# G3-Sensor.net
KiCad netlist of a schematic drawn in Altium Designer
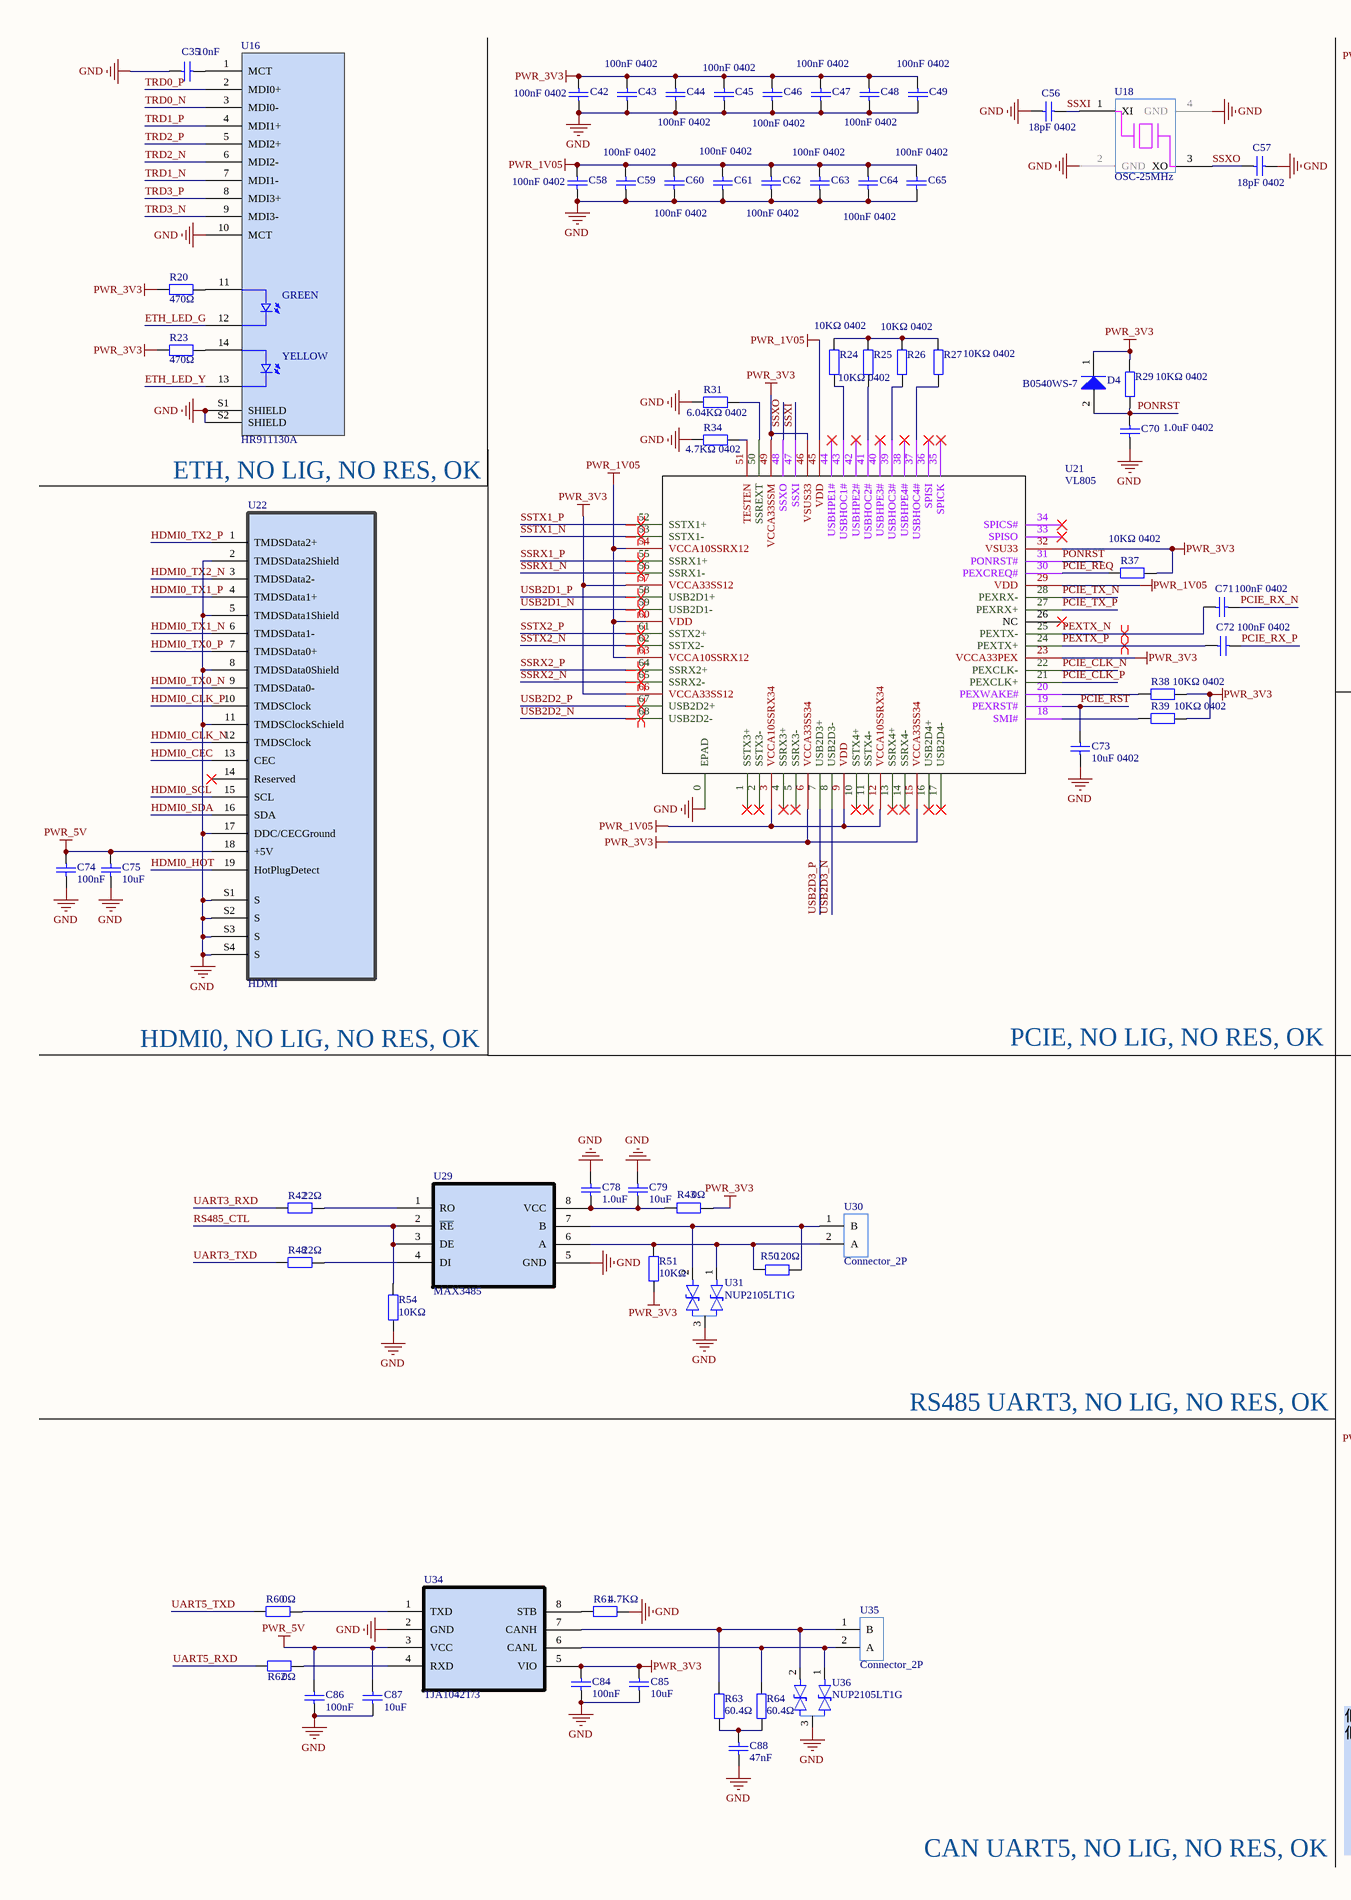
[diagram p0: G3-Sensor.SchDoc, left]
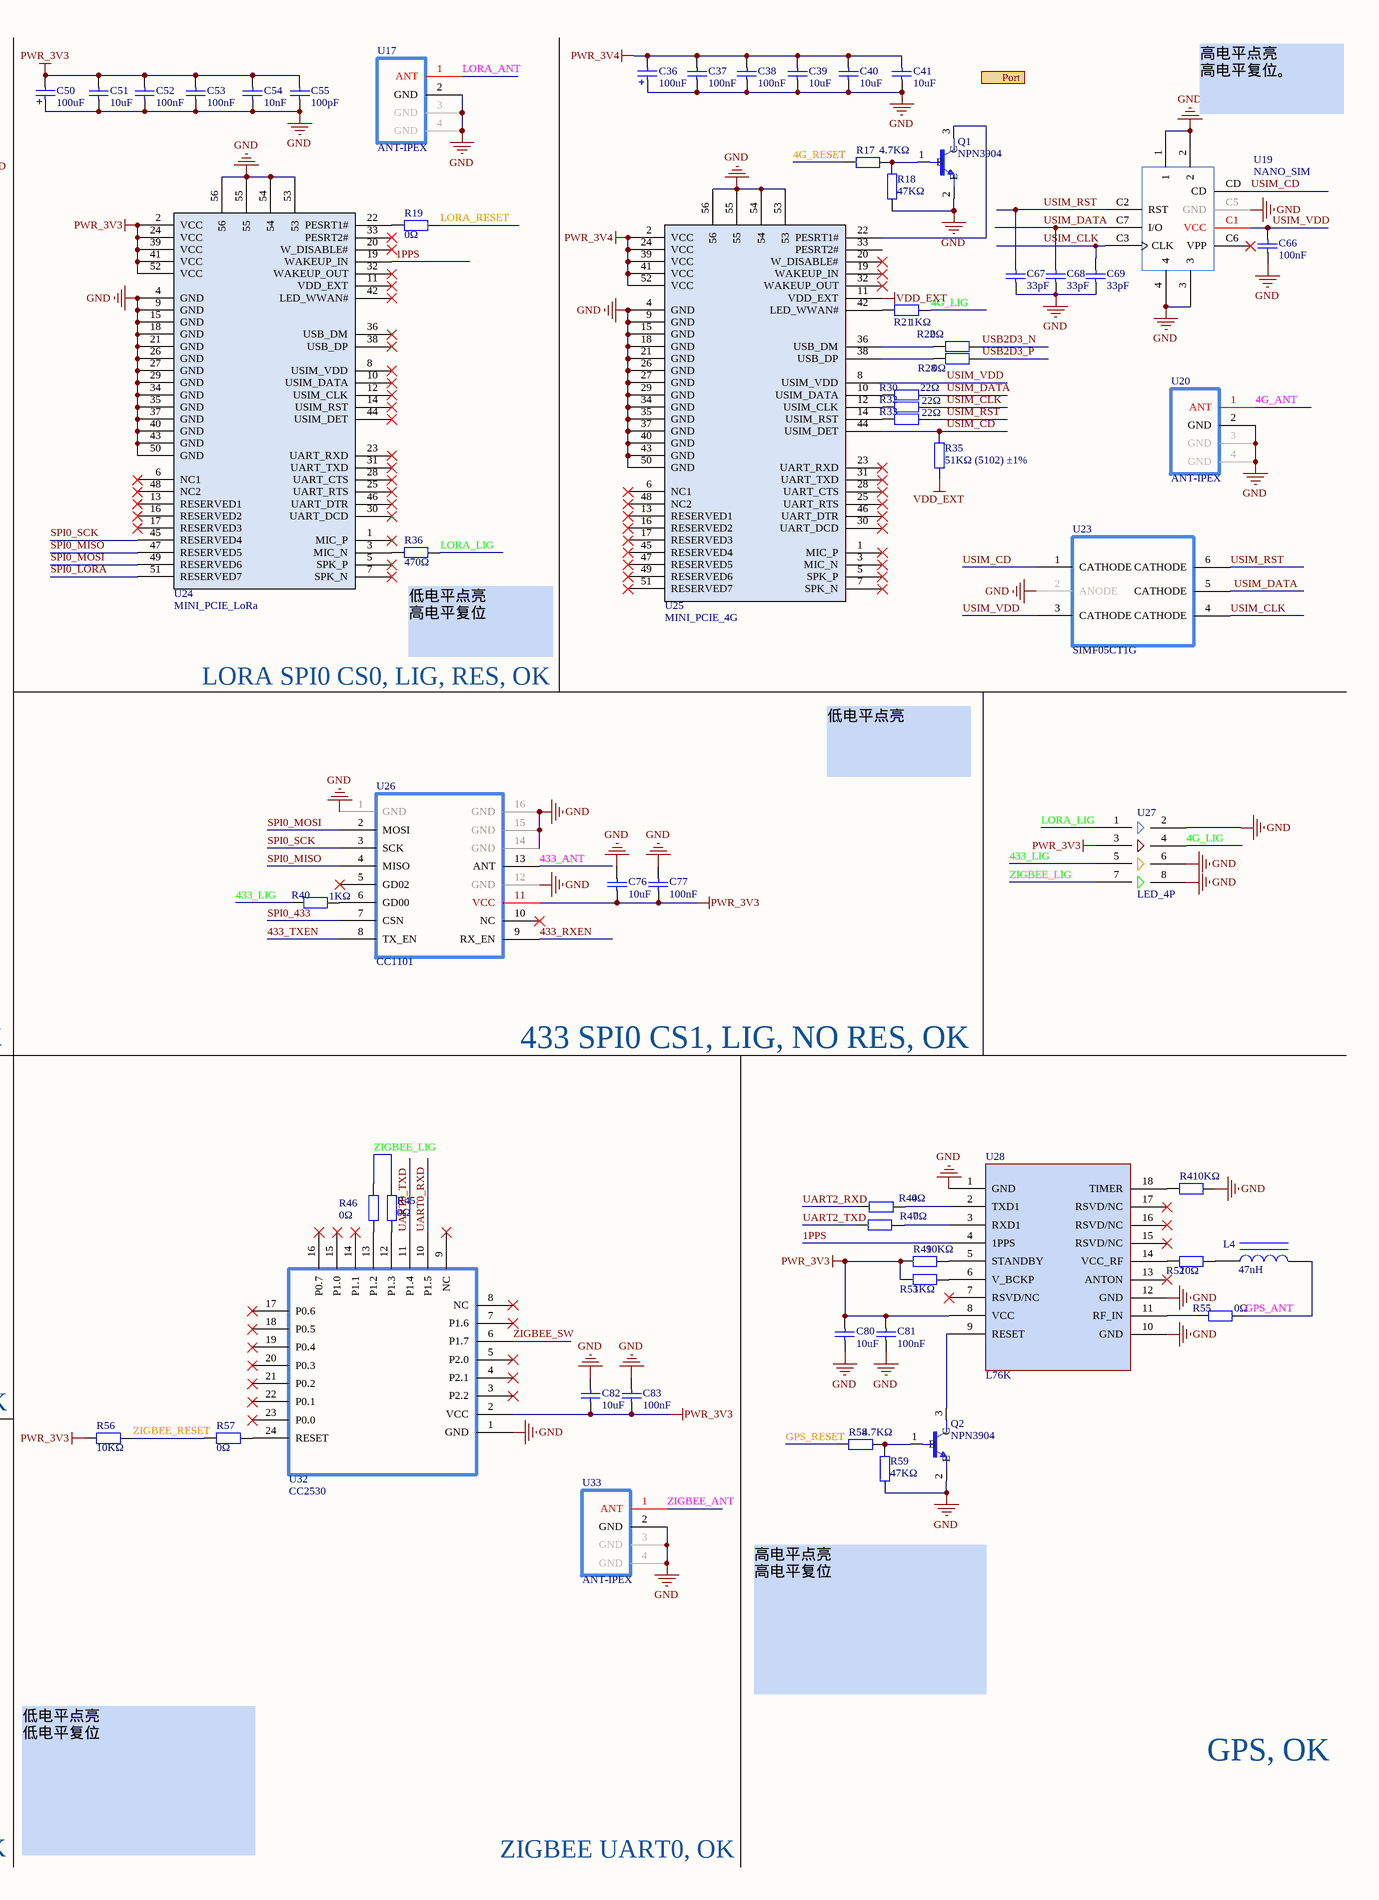
[diagram p1: G3-Sensor.SchDoc, right]

(export (version "E")
  (design (tool "Eeschema 10.0.6"))
  (components
    (comp (ref "C35")
      (value "10nF")
      (footprint "0402_C")
      (description "贴片电容")
      (libsource (lib "Miscellaneous Devices LC") (part "0402 10nF (103) 10% 50V"))
    )
    (comp (ref "C36")
      (value "100uF")
      (footprint "CASE-B_3528")
      (description "钽电容")
      (libsource (lib "Miscellaneous Devices LC") (part "3528 100uF (107) 10% 6.3V"))
    )
    (comp (ref "C37")
      (value "100nF")
      (footprint "1206_C")
      (description "贴片电容")
      (libsource (lib "Miscellaneous Devices LC") (part "1206 100nF (104) 10% 50V"))
    )
    (comp (ref "C38")
      (value "100nF")
      (footprint "1206_C")
      (description "贴片电容")
      (libsource (lib "Miscellaneous Devices LC") (part "1206 100nF (104) 10% 50V"))
    )
    (comp (ref "C39")
      (value "10uF")
      (footprint "1206_C")
      (description "贴片电容")
      (libsource (lib "Miscellaneous Devices LC") (part "1206 10uF (106) 10% 50V"))
    )
    (comp (ref "C40")
      (value "10uF")
      (footprint "1206_C")
      (description "贴片电容")
      (libsource (lib "Miscellaneous Devices LC") (part "1206 10uF (106) 10% 50V"))
    )
    (comp (ref "C41")
      (value "10uF")
      (footprint "1206_C")
      (description "贴片电容")
      (libsource (lib "Miscellaneous Devices LC") (part "1206 10uF (106) 10% 50V"))
    )
    (comp (ref "C42")
      (value "100nF 0402")
      (footprint "0402_C")
      (description "贴片电容")
      (libsource (lib "Miscellaneous Devices LC") (part "0402 100nF (104) 10% 16V"))
    )
    (comp (ref "C43")
      (value "100nF 0402")
      (footprint "0402_C")
      (description "贴片电容")
      (libsource (lib "Miscellaneous Devices LC") (part "0402 100nF (104) 10% 16V"))
    )
    (comp (ref "C44")
      (value "100nF 0402")
      (footprint "0402_C")
      (description "贴片电容")
      (libsource (lib "Miscellaneous Devices LC") (part "0402 100nF (104) 10% 16V"))
    )
    (comp (ref "C45")
      (value "100nF 0402")
      (footprint "0402_C")
      (description "贴片电容")
      (libsource (lib "Miscellaneous Devices LC") (part "0402 100nF (104) 10% 16V"))
    )
    (comp (ref "C46")
      (value "100nF 0402")
      (footprint "0402_C")
      (description "贴片电容")
      (libsource (lib "Miscellaneous Devices LC") (part "0402 100nF (104) 10% 16V"))
    )
    (comp (ref "C47")
      (value "100nF 0402")
      (footprint "0402_C")
      (description "贴片电容")
      (libsource (lib "Miscellaneous Devices LC") (part "0402 100nF (104) 10% 16V"))
    )
    (comp (ref "C48")
      (value "100nF 0402")
      (footprint "0402_C")
      (description "贴片电容")
      (libsource (lib "Miscellaneous Devices LC") (part "0402 100nF (104) 10% 16V"))
    )
    (comp (ref "C49")
      (value "100nF 0402")
      (footprint "0402_C")
      (description "贴片电容")
      (libsource (lib "Miscellaneous Devices LC") (part "0402 100nF (104) 10% 16V"))
    )
    (comp (ref "C50")
      (value "100uF")
      (footprint "CASE-B_3528")
      (description "钽电容")
      (libsource (lib "Miscellaneous Devices LC") (part "3528 100uF (107) 10% 6.3V"))
    )
    (comp (ref "C51")
      (value "10uF")
      (footprint "0402_C")
      (description "贴片电容")
      (libsource (lib "Miscellaneous Devices LC") (part "0402 10uF (106) 20% 6.3V"))
    )
    (comp (ref "C52")
      (value "100nF")
      (footprint "0402_C")
      (description "贴片电容")
      (libsource (lib "Miscellaneous Devices LC") (part "0402 100nF (104) 10% 16V"))
    )
    (comp (ref "C53")
      (value "100nF")
      (footprint "0402_C")
      (description "贴片电容")
      (libsource (lib "Miscellaneous Devices LC") (part "0402 100nF (104) 10% 16V"))
    )
    (comp (ref "C54")
      (value "10nF")
      (footprint "0402_C")
      (description "贴片电容")
      (libsource (lib "Miscellaneous Devices LC") (part "0402 10nF (103) 10% 50V"))
    )
    (comp (ref "C55")
      (value "100pF")
      (footprint "0402_C")
      (description "贴片电容")
      (libsource (lib "Miscellaneous Devices LC") (part "0402 100pF (101) 5% 50V"))
    )
    (comp (ref "C56")
      (value "18pF 0402")
      (footprint "0402_C")
      (description "贴片电容")
      (libsource (lib "Miscellaneous Devices LC") (part "0402 18pF (180) 5% 50V"))
    )
    (comp (ref "C57")
      (value "18pF 0402")
      (footprint "0402_C")
      (description "贴片电容")
      (libsource (lib "Miscellaneous Devices LC") (part "0402 18pF (180) 5% 50V"))
    )
    (comp (ref "C58")
      (value "100nF 0402")
      (footprint "0402_C")
      (description "贴片电容")
      (libsource (lib "Miscellaneous Devices LC") (part "0402 100nF (104) 10% 16V"))
    )
    (comp (ref "C59")
      (value "100nF 0402")
      (footprint "0402_C")
      (description "贴片电容")
      (libsource (lib "Miscellaneous Devices LC") (part "0402 100nF (104) 10% 16V"))
    )
    (comp (ref "C60")
      (value "100nF 0402")
      (footprint "0402_C")
      (description "贴片电容")
      (libsource (lib "Miscellaneous Devices LC") (part "0402 100nF (104) 10% 16V"))
    )
    (comp (ref "C61")
      (value "100nF 0402")
      (footprint "0402_C")
      (description "贴片电容")
      (libsource (lib "Miscellaneous Devices LC") (part "0402 100nF (104) 10% 16V"))
    )
    (comp (ref "C62")
      (value "100nF 0402")
      (footprint "0402_C")
      (description "贴片电容")
      (libsource (lib "Miscellaneous Devices LC") (part "0402 100nF (104) 10% 16V"))
    )
    (comp (ref "C63")
      (value "100nF 0402")
      (footprint "0402_C")
      (description "贴片电容")
      (libsource (lib "Miscellaneous Devices LC") (part "0402 100nF (104) 10% 16V"))
    )
    (comp (ref "C64")
      (value "100nF 0402")
      (footprint "0402_C")
      (description "贴片电容")
      (libsource (lib "Miscellaneous Devices LC") (part "0402 100nF (104) 10% 16V"))
    )
    (comp (ref "C65")
      (value "100nF 0402")
      (footprint "0402_C")
      (description "贴片电容")
      (libsource (lib "Miscellaneous Devices LC") (part "0402 100nF (104) 10% 16V"))
    )
    (comp (ref "C66")
      (value "100nF")
      (footprint "0402_C")
      (description "贴片电容")
      (libsource (lib "Miscellaneous Devices LC") (part "0402 100nF (104) 10% 16V"))
    )
    (comp (ref "C67")
      (value "33pF")
      (footprint "0402_C")
      (description "贴片电容")
      (libsource (lib "Miscellaneous Devices LC") (part "0402 33pF (330) 5% 50V"))
    )
    (comp (ref "C68")
      (value "33pF")
      (footprint "0402_C")
      (description "贴片电容")
      (libsource (lib "Miscellaneous Devices LC") (part "0402 33pF (330) 5% 50V"))
    )
    (comp (ref "C69")
      (value "33pF")
      (footprint "0402_C")
      (description "贴片电容")
      (libsource (lib "Miscellaneous Devices LC") (part "0402 33pF (330) 5% 50V"))
    )
    (comp (ref "C70")
      (value "1.0uF 0402")
      (footprint "0402_C")
      (description "贴片电容")
      (libsource (lib "Miscellaneous Devices LC") (part "0402 1.0uF (105) 10% 25V"))
    )
    (comp (ref "C71")
      (value "100nF 0402")
      (footprint "0402_C")
      (description "贴片电容")
      (libsource (lib "Miscellaneous Devices LC") (part "0402 100nF (104) 10% 16V"))
    )
    (comp (ref "C72")
      (value "100nF 0402")
      (footprint "0402_C")
      (description "贴片电容")
      (libsource (lib "Miscellaneous Devices LC") (part "0402 100nF (104) 10% 16V"))
    )
    (comp (ref "C73")
      (value "10uF 0402")
      (footprint "0402_C")
      (description "贴片电容")
      (libsource (lib "Miscellaneous Devices LC") (part "0402 10uF (106) 20% 6.3V"))
    )
    (comp (ref "C74")
      (value "100nF")
      (footprint "0402_C")
      (description "贴片电容")
      (libsource (lib "Miscellaneous Devices LC") (part "0402 100nF (104) 10% 16V"))
    )
    (comp (ref "C75")
      (value "10uF")
      (footprint "0402_C")
      (description "贴片电容")
      (libsource (lib "Miscellaneous Devices LC") (part "0402 10uF (106) 20% 6.3V"))
    )
    (comp (ref "C76")
      (value "10uF")
      (footprint "0402_C")
      (description "贴片电容")
      (libsource (lib "Miscellaneous Devices LC") (part "0402 10uF (106) 20% 6.3V"))
    )
    (comp (ref "C77")
      (value "100nF")
      (footprint "0402_C")
      (description "贴片电容")
      (libsource (lib "Miscellaneous Devices LC") (part "0402 100nF (104) 10% 16V"))
    )
    (comp (ref "C78")
      (value "1.0uF")
      (footprint "0402_C")
      (description "贴片电容")
      (libsource (lib "Miscellaneous Devices LC") (part "0402 1.0uF (105) 10% 25V"))
    )
    (comp (ref "C79")
      (value "10uF")
      (footprint "0402_C")
      (description "贴片电容")
      (libsource (lib "Miscellaneous Devices LC") (part "0402 10uF (106) 20% 6.3V"))
    )
    (comp (ref "C80")
      (value "10uF")
      (footprint "0402_C")
      (description "贴片电容")
      (libsource (lib "Miscellaneous Devices LC") (part "0402 10uF (106) 20% 6.3V"))
    )
    (comp (ref "C81")
      (value "100nF")
      (footprint "0402_C")
      (description "贴片电容")
      (libsource (lib "Miscellaneous Devices LC") (part "0402 100nF (104) 10% 16V"))
    )
    (comp (ref "C82")
      (value "10uF")
      (footprint "0402_C")
      (description "贴片电容")
      (libsource (lib "Miscellaneous Devices LC") (part "0402 10uF (106) 20% 6.3V"))
    )
    (comp (ref "C83")
      (value "100nF")
      (footprint "0402_C")
      (description "贴片电容")
      (libsource (lib "Miscellaneous Devices LC") (part "0402 100nF (104) 10% 16V"))
    )
    (comp (ref "C84")
      (value "100nF")
      (footprint "0402_C")
      (description "贴片电容")
      (libsource (lib "Miscellaneous Devices LC") (part "0402 100nF (104) 10% 16V"))
    )
    (comp (ref "C85")
      (value "10uF")
      (footprint "0402_C")
      (description "贴片电容")
      (libsource (lib "Miscellaneous Devices LC") (part "0402 10uF (106) 20% 6.3V"))
    )
    (comp (ref "C86")
      (value "100nF")
      (footprint "0402_C")
      (description "贴片电容")
      (libsource (lib "Miscellaneous Devices LC") (part "0402 100nF (104) 10% 16V"))
    )
    (comp (ref "C87")
      (value "10uF")
      (footprint "0402_C")
      (description "贴片电容")
      (libsource (lib "Miscellaneous Devices LC") (part "0402 10uF (106) 20% 6.3V"))
    )
    (comp (ref "C88")
      (value "47nF")
      (footprint "0402_C")
      (description "贴片电容")
      (libsource (lib "Miscellaneous Devices LC") (part "0402 100nF (104) 10% 16V"))
    )
    (comp (ref "D4") (value "B0540WS-7") (footprint "B0540WS-7") (libsource (lib "Mars") (part "B0540WS-7")))
    (comp (ref "L4")
      (value "47nH")
      (footprint "0603_L")
      (description "贴片电感")
      (libsource (lib "Miscellaneous Devices LC") (part "0603 47nH"))
    )
    (comp (ref "Q1")
      (value "NPN3904")
      (footprint "NPN3904")
      (description "Bipolar _BJT_ Transistor NPN 40V 200mA 300MHz 300mW Surface Mount SOT-23-3 _TO-236_")
      (fields (field (name "MF") "ON Semiconductor") (field (name "MP") "MMBT3904LT1G"))
      (libsource (lib "Sensor") (part "NPN3904"))
    )
    (comp (ref "Q2")
      (value "NPN3904")
      (footprint "NPN3904")
      (description "Bipolar _BJT_ Transistor NPN 40V 200mA 300MHz 300mW Surface Mount SOT-23-3 _TO-236_")
      (fields (field (name "MF") "ON Semiconductor") (field (name "MP") "MMBT3904LT1G"))
      (libsource (lib "Sensor") (part "NPN3904"))
    )
    (comp (ref "R17")
      (value "4.7KΩ")
      (footprint "0402_R")
      (description "贴片电阻")
      (libsource (lib "Miscellaneous Devices LC") (part "0402 4.7KΩ (4701) 1%"))
    )
    (comp (ref "R18")
      (value "47KΩ")
      (footprint "0402_R")
      (description "贴片电阻")
      (libsource (lib "Miscellaneous Devices LC") (part "0402 47KΩ (4702) 1%"))
    )
    (comp (ref "R19")
      (value "0Ω")
      (footprint "0402_R")
      (description "贴片电阻")
      (libsource (lib "") (part "0402 0Ω (0R0) 1%_2"))
    )
    (comp (ref "R20")
      (value "470Ω")
      (footprint "0402_R")
      (description "贴片电阻")
      (libsource (lib "Miscellaneous Devices LC") (part "0402 470Ω (4700) 1%"))
    )
    (comp (ref "R21")
      (value "1KΩ")
      (footprint "0402_R")
      (description "贴片电阻")
      (libsource (lib "Miscellaneous Devices LC") (part "0402 1KΩ (1001) 1%"))
    )
    (comp (ref "R22")
      (value "0Ω")
      (footprint "0402_R")
      (description "贴片电阻")
      (libsource (lib "") (part "0402 0Ω (0R0) 1%_2"))
    )
    (comp (ref "R23")
      (value "470Ω")
      (footprint "0402_R")
      (description "贴片电阻")
      (libsource (lib "Miscellaneous Devices LC") (part "0402 470Ω (4700) 1%"))
    )
    (comp (ref "R24")
      (value "10KΩ 0402")
      (footprint "0402_R")
      (description "贴片电阻")
      (libsource (lib "Miscellaneous Devices LC") (part "0402 10KΩ (1002) 1%"))
    )
    (comp (ref "R25")
      (value "10KΩ 0402")
      (footprint "0402_R")
      (description "贴片电阻")
      (libsource (lib "Miscellaneous Devices LC") (part "0402 10KΩ (1002) 1%"))
    )
    (comp (ref "R26")
      (value "10KΩ 0402")
      (footprint "0402_R")
      (description "贴片电阻")
      (libsource (lib "Miscellaneous Devices LC") (part "0402 10KΩ (1002) 1%"))
    )
    (comp (ref "R27")
      (value "10KΩ 0402")
      (footprint "0402_R")
      (description "贴片电阻")
      (libsource (lib "Miscellaneous Devices LC") (part "0402 10KΩ (1002) 1%"))
    )
    (comp (ref "R28")
      (value "0Ω")
      (footprint "0402_R")
      (description "贴片电阻")
      (libsource (lib "Miscellaneous Devices LC") (part "0402 0Ω (0R0) 1%"))
    )
    (comp (ref "R29")
      (value "10KΩ 0402")
      (footprint "0402_R")
      (description "贴片电阻")
      (libsource (lib "Miscellaneous Devices LC") (part "0402 10KΩ (1002) 1%"))
    )
    (comp (ref "R30")
      (value "22Ω")
      (footprint "0402_R")
      (description "贴片电阻")
      (libsource (lib "") (part "0402 22Ω (22R0) 1%_1"))
    )
    (comp (ref "R31")
      (value "6.04KΩ 0402")
      (footprint "0402_R")
      (description "贴片电阻")
      (libsource (lib "Miscellaneous Devices LC") (part "0402 5.6KΩ (5601) 1%"))
    )
    (comp (ref "R32")
      (value "22Ω")
      (footprint "0402_R")
      (description "贴片电阻")
      (libsource (lib "") (part "0402 22Ω (22R0) 1%_1"))
    )
    (comp (ref "R33")
      (value "22Ω")
      (footprint "0402_R")
      (description "贴片电阻")
      (libsource (lib "") (part "0402 22Ω (22R0) 1%_1"))
    )
    (comp (ref "R34")
      (value "4.7KΩ 0402")
      (footprint "0402_R")
      (description "贴片电阻")
      (libsource (lib "") (part "0402 4.7KΩ (4701) 1%_1"))
    )
    (comp (ref "R35")
      (value "51KΩ (5102) ±1%")
      (footprint "0402_R")
      (description "贴片电阻")
      (libsource (lib "Miscellaneous Devices LC") (part "0402 51KΩ (5102) 1%"))
    )
    (comp (ref "R36")
      (value "470Ω")
      (footprint "0402_R")
      (description "贴片电阻")
      (libsource (lib "Miscellaneous Devices LC") (part "0402 470Ω (4700) 1%"))
    )
    (comp (ref "R37")
      (value "10KΩ 0402")
      (footprint "0402_R")
      (description "贴片电阻")
      (libsource (lib "") (part "0402 10KΩ (1002) 1%_1"))
    )
    (comp (ref "R38")
      (value "10KΩ 0402")
      (footprint "0402_R")
      (description "贴片电阻")
      (libsource (lib "") (part "0402 10KΩ (1002) 1%_1"))
    )
    (comp (ref "R39")
      (value "10KΩ 0402")
      (footprint "0402_R")
      (description "贴片电阻")
      (libsource (lib "") (part "0402 10KΩ (1002) 1%_1"))
    )
    (comp (ref "R40")
      (value "1KΩ")
      (footprint "0402_R")
      (description "贴片电阻")
      (libsource (lib "Miscellaneous Devices LC") (part "0402 1KΩ (1001) 1%"))
    )
    (comp (ref "R41")
      (value "10KΩ")
      (footprint "0402_R")
      (description "贴片电阻")
      (libsource (lib "") (part "0402 10KΩ (1002) 1%_1"))
    )
    (comp (ref "R42")
      (value "22Ω")
      (footprint "0402_R")
      (description "贴片电阻")
      (libsource (lib "") (part "0402 22Ω (22R0) 1%_1"))
    )
    (comp (ref "R43")
      (value "0Ω")
      (footprint "0402_R")
      (description "贴片电阻")
      (libsource (lib "Miscellaneous Devices LC") (part "0402 0Ω (0R0) 1%"))
    )
    (comp (ref "R44")
      (value "0Ω")
      (footprint "0402_R")
      (description "贴片电阻")
      (libsource (lib "Miscellaneous Devices LC") (part "0402 0Ω (0R0) 1%"))
    )
    (comp (ref "R45")
      (value "0Ω")
      (footprint "0402_R")
      (description "贴片电阻")
      (libsource (lib "") (part "0402 0Ω (0R0) 1%_1"))
    )
    (comp (ref "R46")
      (value "0Ω")
      (footprint "0402_R")
      (description "贴片电阻")
      (libsource (lib "") (part "0402 0Ω (0R0) 1%_1"))
    )
    (comp (ref "R47")
      (value "0Ω")
      (footprint "0402_R")
      (description "贴片电阻")
      (libsource (lib "Miscellaneous Devices LC") (part "0402 0Ω (0R0) 1%"))
    )
    (comp (ref "R48")
      (value "22Ω")
      (footprint "0402_R")
      (description "贴片电阻")
      (libsource (lib "") (part "0402 22Ω (22R0) 1%_1"))
    )
    (comp (ref "R49")
      (value "10KΩ")
      (footprint "0402_R")
      (description "贴片电阻")
      (libsource (lib "") (part "0402 10KΩ (1002) 1%_1"))
    )
    (comp (ref "R50")
      (value "120Ω")
      (footprint "0402_R")
      (description "贴片电阻")
      (libsource (lib "Miscellaneous Devices LC") (part "0402 120Ω (1200) 1%"))
    )
    (comp (ref "R51")
      (value "10KΩ")
      (footprint "0402_R")
      (description "贴片电阻")
      (libsource (lib "Miscellaneous Devices LC") (part "0402 10KΩ (1002) 1%"))
    )
    (comp (ref "R52")
      (value "10Ω")
      (footprint "0402_R")
      (description "贴片电阻")
      (libsource (lib "Miscellaneous Devices LC") (part "0402 10Ω (10R0) 1%"))
    )
    (comp (ref "R53")
      (value "1KΩ")
      (footprint "0402_R")
      (description "贴片电阻")
      (libsource (lib "Miscellaneous Devices LC") (part "0402 1KΩ (1001) 1%"))
    )
    (comp (ref "R54")
      (value "10KΩ")
      (footprint "0402_R")
      (description "贴片电阻")
      (libsource (lib "Miscellaneous Devices LC") (part "0402 10KΩ (1002) 1%"))
    )
    (comp (ref "R55")
      (value "0Ω")
      (footprint "0402_R")
      (description "贴片电阻")
      (libsource (lib "Miscellaneous Devices LC") (part "0402 0Ω (0R0) 1%"))
    )
    (comp (ref "R56")
      (value "10KΩ")
      (footprint "0402_R")
      (description "贴片电阻")
      (libsource (lib "") (part "0402 10KΩ (1002) 1%_1"))
    )
    (comp (ref "R57")
      (value "0Ω")
      (footprint "0402_R")
      (description "贴片电阻")
      (libsource (lib "") (part "0402 0Ω (0R0) 1%_2"))
    )
    (comp (ref "R58")
      (value "4.7KΩ")
      (footprint "0402_R")
      (description "贴片电阻")
      (libsource (lib "Miscellaneous Devices LC") (part "0402 4.7KΩ (4701) 1%"))
    )
    (comp (ref "R59")
      (value "47KΩ")
      (footprint "0402_R")
      (description "贴片电阻")
      (libsource (lib "Miscellaneous Devices LC") (part "0402 47KΩ (4702) 1%"))
    )
    (comp (ref "R60")
      (value "0Ω")
      (footprint "0402_R")
      (description "贴片电阻")
      (libsource (lib "Miscellaneous Devices LC") (part "0402 0Ω (0R0) 1%"))
    )
    (comp (ref "R61")
      (value "4.7KΩ")
      (footprint "0402_R")
      (description "贴片电阻")
      (libsource (lib "Miscellaneous Devices LC") (part "0402 4.7KΩ (4701) 1%"))
    )
    (comp (ref "R62")
      (value "0Ω")
      (footprint "0402_R")
      (description "贴片电阻")
      (libsource (lib "Miscellaneous Devices LC") (part "0402 0Ω (0R0) 1%"))
    )
    (comp (ref "R63")
      (value "60.4Ω")
      (footprint "0402_R")
      (description "贴片电阻")
      (libsource (lib "Miscellaneous Devices LC") (part "0402 22Ω (22R0) 1%"))
    )
    (comp (ref "R64")
      (value "60.4Ω")
      (footprint "0402_R")
      (description "贴片电阻")
      (libsource (lib "Miscellaneous Devices LC") (part "0402 22Ω (22R0) 1%"))
    )
    (comp (ref "U16")
      (value "HR911130A")
      (footprint "HR911130A")
      (description "RJ45")
      (libsource (lib "bohao") (part "HR911130A"))
    )
    (comp (ref "U17")
      (value "ANT-IPEX")
      (footprint "ANT-IPEX")
      (description "ANT")
      (libsource (lib "Sensor") (part "ANT-IPEX"))
    )
    (comp (ref "U18")
      (value "OSC-25MHz")
      (footprint "OSC-25MHz")
      (description "Passive crystal oscillator")
      (libsource (lib "Mars") (part "OSC-25MHz"))
    )
    (comp (ref "U19")
      (value "NANO_SIM")
      (footprint "NANO_SIM")
      (description "4G Card Slot")
      (libsource (lib "bohao") (part "NANO_SIM"))
    )
    (comp (ref "U20")
      (value "ANT-IPEX")
      (footprint "ANT-IPEX")
      (description "ANT")
      (libsource (lib "Sensor") (part "ANT-IPEX"))
    )
    (comp (ref "U21")
      (value "VL805")
      (footprint "VL805")
      (description "PCIe to USB3.0")
      (libsource (lib "Mars") (part "VL805"))
    )
    (comp (ref "U22") (value "HDMI") (footprint "HDMI") (libsource (lib "bohao") (part "HDMI")))
    (comp (ref "U23")
      (value "SIMF05CT1G")
      (footprint "SMF05CT1G")
      (libsource (lib "bohao") (part "SIMF05CT1G"))
    )
    (comp (ref "U24")
      (value "MINI_PCIE_LoRa")
      (footprint "MINI-PCIE")
      (description "LoRa, 4G")
      (libsource (lib "bohao") (part "MINI_PCIE"))
    )
    (comp (ref "U25")
      (value "MINI_PCIE_4G")
      (footprint "MINI-PCIE")
      (description "LoRa, 4G")
      (libsource (lib "bohao") (part "MINI_PCIE"))
    )
    (comp (ref "U26")
      (value "CC1101")
      (footprint "CC1101")
      (description "433Mhz")
      (libsource (lib "bohao") (part "CC1101"))
    )
    (comp (ref "U27")
      (value "LED_4P")
      (footprint "LED_4P")
      (description "LED")
      (libsource (lib "bohao") (part "LED_4P"))
    )
    (comp (ref "U28")
      (value "L76K")
      (footprint "L76K")
      (description "GPS BEIDOU")
      (libsource (lib "bohao") (part "L76K"))
    )
    (comp (ref "U29")
      (value "MAX3485")
      (footprint "MAX3485")
      (description "UART = RS485")
      (libsource (lib "bohao") (part "MAX3485"))
    )
    (comp (ref "U30")
      (value "Connector_2P")
      (footprint "CONNECTOR_2P")
      (description "Connector for RS485, CAN")
      (libsource (lib "bohao") (part "Connector_2P"))
    )
    (comp (ref "U31")
      (value "NUP2105LT1G")
      (footprint "NUP2105LT1G")
      (libsource (lib "bohao") (part "NUP2105LT1G"))
    )
    (comp (ref "U32")
      (value "CC2530")
      (footprint "CC2530")
      (description "ZigBee 2.4GHz")
      (libsource (lib "bohao") (part "CC2530"))
    )
    (comp (ref "U33")
      (value "ANT-IPEX")
      (footprint "ANT-IPEX")
      (description "ANT")
      (libsource (lib "Sensor") (part "ANT-IPEX"))
    )
    (comp (ref "U34")
      (value "TJA1042T/3")
      (footprint "TJA1042T")
      (description "UART = CAN")
      (libsource (lib "bohao") (part "TJA1042T/3"))
    )
    (comp (ref "U35")
      (value "Connector_2P")
      (footprint "CONNECTOR_2P")
      (description "Connector for RS485, CAN")
      (libsource (lib "bohao") (part "Connector_2P"))
    )
    (comp (ref "U36")
      (value "NUP2105LT1G")
      (footprint "NUP2105LT1G")
      (libsource (lib "bohao") (part "NUP2105LT1G"))
    )
  )
  (nets
    (net (code "1") (name "/1PPS") (class "Default")
      (node (ref "U24") (pin "19") (pinfunction "WAKEUP_IN_19") (pintype "passive"))
      (node (ref "U28") (pin "4") (pinfunction "1PPS_4") (pintype "passive"))
    )
    (net (code "2") (name "/4G_ANT") (class "Default")
      (node (ref "U20") (pin "1") (pinfunction "ANT_1") (pintype "passive"))
    )
    (net (code "3") (name "/4G_LIG") (class "Default")
      (node (ref "R21") (pin "2") (pinfunction "2_2") (pintype "passive"))
      (node (ref "U27") (pin "4") (pintype "passive"))
    )
    (net (code "4") (name "/4G_RESET") (class "Default")
      (node (ref "R17") (pin "1") (pinfunction "1_1") (pintype "passive"))
    )
    (net (code "5") (name "/433_ANT") (class "Default")
      (node (ref "U26") (pin "13") (pinfunction "ANT_13") (pintype "passive"))
    )
    (net (code "6") (name "/433_LIG") (class "Default")
      (node (ref "R40") (pin "1") (pinfunction "1_1") (pintype "passive"))
      (node (ref "U27") (pin "5") (pintype "passive"))
    )
    (net (code "7") (name "/433_RXEN") (class "Default")
      (node (ref "U26") (pin "9") (pinfunction "RX_EN_9") (pintype "passive"))
    )
    (net (code "8") (name "/433_TXEN") (class "Default")
      (node (ref "U26") (pin "8") (pinfunction "TX_EN_8") (pintype "passive"))
    )
    (net (code "9") (name "/ETH_LED_G") (class "Default")
      (node (ref "U16") (pin "12") (pinfunction "12_12") (pintype "passive"))
    )
    (net (code "10") (name "/ETH_LED_Y") (class "Default")
      (node (ref "U16") (pin "13") (pinfunction "13_13") (pintype "passive"))
    )
    (net (code "11") (name "/GPS_ANT") (class "Default")
      (node (ref "L4") (pin "2") (pinfunction "2_2") (pintype "passive"))
      (node (ref "R55") (pin "2") (pinfunction "2_2") (pintype "passive"))
    )
    (net (code "12") (name "/GPS_RESET") (class "Default")
      (node (ref "R58") (pin "1") (pinfunction "1_1") (pintype "passive"))
    )
    (net (code "13") (name "/HDMI0_CEC") (class "Default")
      (node (ref "U22") (pin "13") (pinfunction "CEC_13") (pintype "passive"))
    )
    (net (code "14") (name "/HDMI0_CLK_N") (class "Default")
      (node (ref "U22") (pin "12") (pinfunction "TMDSClock_12") (pintype "passive"))
    )
    (net (code "15") (name "/HDMI0_CLK_P") (class "Default")
      (node (ref "U22") (pin "10") (pinfunction "TMDSClock_10") (pintype "passive"))
    )
    (net (code "16") (name "/HDMI0_HOT") (class "Default")
      (node (ref "U22") (pin "19") (pinfunction "HotPlugDetect_19") (pintype "passive"))
    )
    (net (code "17") (name "/HDMI0_SCL") (class "Default")
      (node (ref "U22") (pin "15") (pinfunction "SCL_15") (pintype "passive"))
    )
    (net (code "18") (name "/HDMI0_SDA") (class "Default")
      (node (ref "U22") (pin "16") (pinfunction "SDA_16") (pintype "passive"))
    )
    (net (code "19") (name "/HDMI0_TX0_N") (class "Default")
      (node (ref "U22") (pin "9") (pinfunction "TMDSData0-_9") (pintype "passive"))
    )
    (net (code "20") (name "/HDMI0_TX0_P") (class "Default")
      (node (ref "U22") (pin "7") (pinfunction "TMDSData0+_7") (pintype "passive"))
    )
    (net (code "21") (name "/HDMI0_TX1_N") (class "Default")
      (node (ref "U22") (pin "6") (pinfunction "TMDSData1-_6") (pintype "passive"))
    )
    (net (code "22") (name "/HDMI0_TX1_P") (class "Default")
      (node (ref "U22") (pin "4") (pinfunction "TMDSData1+_4") (pintype "passive"))
    )
    (net (code "23") (name "/HDMI0_TX2_N") (class "Default")
      (node (ref "U22") (pin "3") (pinfunction "TMDSData2-_3") (pintype "passive"))
    )
    (net (code "24") (name "/HDMI0_TX2_P") (class "Default")
      (node (ref "U22") (pin "1") (pinfunction "TMDSData2+_1") (pintype "passive"))
    )
    (net (code "25") (name "/LORA_ANT") (class "Default")
      (node (ref "U17") (pin "1") (pinfunction "ANT_1") (pintype "passive"))
    )
    (net (code "26") (name "/LORA_LIG") (class "Default")
      (node (ref "R36") (pin "2") (pinfunction "2_2") (pintype "passive"))
      (node (ref "U27") (pin "1") (pintype "passive"))
    )
    (net (code "27") (name "/LORA_RESET") (class "Default")
      (node (ref "R19") (pin "1") (pinfunction "1_1") (pintype "passive"))
    )
    (net (code "28") (name "/PCIE_CLK_N") (class "Default")
      (node (ref "U21") (pin "22") (pinfunction "PEXCLK-_22") (pintype "passive"))
    )
    (net (code "29") (name "/PCIE_CLK_P") (class "Default")
      (node (ref "U21") (pin "21") (pinfunction "PEXCLK+_21") (pintype "passive"))
    )
    (net (code "30") (name "/PCIE_REQ") (class "Default")
      (node (ref "R37") (pin "1") (pinfunction "1_1") (pintype "passive"))
      (node (ref "U21") (pin "30") (pinfunction "PEXCREQ#_30") (pintype "passive"))
    )
    (net (code "31") (name "/PCIE_RST") (class "Default")
      (node (ref "C73") (pin "2") (pinfunction "2_2") (pintype "passive"))
      (node (ref "U21") (pin "19") (pinfunction "PEXRST#_19") (pintype "passive"))
    )
    (net (code "32") (name "/PCIE_RX_N") (class "Default")
      (node (ref "C71") (pin "2") (pinfunction "2_2") (pintype "passive"))
    )
    (net (code "33") (name "/PCIE_RX_P") (class "Default")
      (node (ref "C72") (pin "2") (pinfunction "2_2") (pintype "passive"))
    )
    (net (code "34") (name "/PCIE_TX_N") (class "Default")
      (node (ref "U21") (pin "28") (pinfunction "PEXRX-_28") (pintype "passive"))
    )
    (net (code "35") (name "/PCIE_TX_P") (class "Default")
      (node (ref "U21") (pin "27") (pinfunction "PEXRX+_27") (pintype "passive"))
    )
    (net (code "36") (name "/PEXTX_N") (class "Default")
      (node (ref "C71") (pin "1") (pinfunction "1_1") (pintype "passive"))
      (node (ref "U21") (pin "25") (pinfunction "PEXTX-_25") (pintype "passive"))
    )
    (net (code "37") (name "/PEXTX_P") (class "Default")
      (node (ref "C72") (pin "1") (pinfunction "1_1") (pintype "passive"))
      (node (ref "U21") (pin "24") (pinfunction "PEXTX+_24") (pintype "passive"))
    )
    (net (code "38") (name "/PONRST") (class "Default")
      (node (ref "C70") (pin "1") (pinfunction "1_1") (pintype "passive"))
      (node (ref "D4") (pin "2") (pinfunction "A_2") (pintype "passive"))
      (node (ref "R29") (pin "1") (pinfunction "1_1") (pintype "passive"))
      (node (ref "U21") (pin "31") (pinfunction "PONRST#_31") (pintype "passive"))
    )
    (net (code "40") (name "/RS485_CTL") (class "Default")
      (node (ref "R54") (pin "2") (pinfunction "2_2") (pintype "passive"))
      (node (ref "U29") (pin "2") (pinfunction "~{RE}_2") (pintype "passive"))
      (node (ref "U29") (pin "3") (pinfunction "DE_3") (pintype "passive"))
    )
    (net (code "41") (name "/SPI0_433") (class "Default")
      (node (ref "U26") (pin "7") (pinfunction "CSN_7") (pintype "passive"))
    )
    (net (code "42") (name "/SPI0_LORA") (class "Default")
      (node (ref "U24") (pin "51") (pinfunction "RESERVED7_51") (pintype "passive"))
    )
    (net (code "43") (name "/SPI0_MISO") (class "Default")
      (node (ref "U24") (pin "47") (pinfunction "RESERVED5_47") (pintype "passive"))
      (node (ref "U26") (pin "4") (pinfunction "MISO_4") (pintype "passive"))
    )
    (net (code "44") (name "/SPI0_MOSI") (class "Default")
      (node (ref "U24") (pin "49") (pinfunction "RESERVED6_49") (pintype "passive"))
      (node (ref "U26") (pin "2") (pinfunction "MOSI_2") (pintype "passive"))
    )
    (net (code "45") (name "/SPI0_SCK") (class "Default")
      (node (ref "U24") (pin "45") (pinfunction "RESERVED4_45") (pintype "passive"))
      (node (ref "U26") (pin "3") (pinfunction "SCK_3") (pintype "passive"))
    )
    (net (code "46") (name "/SSRX1_N") (class "Default")
      (node (ref "U21") (pin "56") (pinfunction "SSRX1-_56") (pintype "passive"))
    )
    (net (code "47") (name "/SSRX1_P") (class "Default")
      (node (ref "U21") (pin "55") (pinfunction "SSRX1+_55") (pintype "passive"))
    )
    (net (code "48") (name "/SSRX2_N") (class "Default")
      (node (ref "U21") (pin "65") (pinfunction "SSRX2-_65") (pintype "passive"))
    )
    (net (code "49") (name "/SSRX2_P") (class "Default")
      (node (ref "U21") (pin "64") (pinfunction "SSRX2+_64") (pintype "passive"))
    )
    (net (code "50") (name "/SSTX1_N") (class "Default")
      (node (ref "U21") (pin "53") (pinfunction "SSTX1-_53") (pintype "passive"))
    )
    (net (code "51") (name "/SSTX1_P") (class "Default")
      (node (ref "U21") (pin "52") (pinfunction "SSTX1+_52") (pintype "passive"))
    )
    (net (code "52") (name "/SSTX2_N") (class "Default")
      (node (ref "U21") (pin "62") (pinfunction "SSTX2-_62") (pintype "passive"))
    )
    (net (code "53") (name "/SSTX2_P") (class "Default")
      (node (ref "U21") (pin "61") (pinfunction "SSTX2+_61") (pintype "passive"))
    )
    (net (code "54") (name "/SSXI") (class "Default")
      (node (ref "C56") (pin "2") (pinfunction "2_2") (pintype "passive"))
      (node (ref "U18") (pin "1") (pinfunction "XI_1") (pintype "passive"))
      (node (ref "U21") (pin "47") (pinfunction "SSXI_47") (pintype "passive"))
    )
    (net (code "55") (name "/SSXO") (class "Default")
      (node (ref "C57") (pin "1") (pinfunction "1_1") (pintype "passive"))
      (node (ref "U18") (pin "3") (pinfunction "XO_3") (pintype "passive"))
      (node (ref "U21") (pin "48") (pinfunction "SSXO_48") (pintype "passive"))
    )
    (net (code "56") (name "/TRD0_N") (class "Default")
      (node (ref "U16") (pin "3") (pinfunction "MDI0-_3") (pintype "passive"))
    )
    (net (code "57") (name "/TRD0_P") (class "Default")
      (node (ref "U16") (pin "2") (pinfunction "MDI0+_2") (pintype "passive"))
    )
    (net (code "58") (name "/TRD1_N") (class "Default")
      (node (ref "U16") (pin "7") (pinfunction "MDI1-_7") (pintype "passive"))
    )
    (net (code "59") (name "/TRD1_P") (class "Default")
      (node (ref "U16") (pin "4") (pinfunction "MDI1+_4") (pintype "passive"))
    )
    (net (code "60") (name "/TRD2_N") (class "Default")
      (node (ref "U16") (pin "6") (pinfunction "MDI2-_6") (pintype "passive"))
    )
    (net (code "61") (name "/TRD2_P") (class "Default")
      (node (ref "U16") (pin "5") (pinfunction "MDI2+_5") (pintype "passive"))
    )
    (net (code "62") (name "/TRD3_N") (class "Default")
      (node (ref "U16") (pin "9") (pinfunction "MDI3-_9") (pintype "passive"))
    )
    (net (code "63") (name "/TRD3_P") (class "Default")
      (node (ref "U16") (pin "8") (pinfunction "MDI3+_8") (pintype "passive"))
    )
    (net (code "64") (name "/UART0_RXD") (class "Default")
      (node (ref "U32") (pin "10") (pinfunction "P1.5_10") (pintype "passive"))
    )
    (net (code "65") (name "/UART0_TXD") (class "Default")
      (node (ref "U32") (pin "11") (pinfunction "P1.4_11") (pintype "passive"))
    )
    (net (code "66") (name "/UART2_RXD") (class "Default")
      (node (ref "R44") (pin "1") (pinfunction "1_1") (pintype "passive"))
    )
    (net (code "67") (name "/UART2_TXD") (class "Default")
      (node (ref "R47") (pin "1") (pinfunction "1_1") (pintype "passive"))
    )
    (net (code "68") (name "/UART3_RXD") (class "Default")
      (node (ref "R42") (pin "1") (pinfunction "1_1") (pintype "passive"))
    )
    (net (code "69") (name "/UART3_TXD") (class "Default")
      (node (ref "R48") (pin "1") (pinfunction "1_1") (pintype "passive"))
    )
    (net (code "70") (name "/UART5_RXD") (class "Default")
      (node (ref "R62") (pin "1") (pinfunction "1_1") (pintype "passive"))
    )
    (net (code "71") (name "/UART5_TXD") (class "Default")
      (node (ref "R60") (pin "1") (pinfunction "1_1") (pintype "passive"))
    )
    (net (code "72") (name "/USB2D1_N") (class "Default")
      (node (ref "U21") (pin "59") (pinfunction "USB2D1-_59") (pintype "passive"))
    )
    (net (code "73") (name "/USB2D1_P") (class "Default")
      (node (ref "U21") (pin "58") (pinfunction "USB2D1+_58") (pintype "passive"))
    )
    (net (code "74") (name "/USB2D2_N") (class "Default")
      (node (ref "U21") (pin "68") (pinfunction "USB2D2-_68") (pintype "passive"))
    )
    (net (code "75") (name "/USB2D2_P") (class "Default")
      (node (ref "U21") (pin "67") (pinfunction "USB2D2+_67") (pintype "passive"))
    )
    (net (code "76") (name "/USB2D3_N") (class "Default")
      (node (ref "R22") (pin "1") (pinfunction "1_1") (pintype "passive"))
      (node (ref "U21") (pin "8") (pinfunction "USB2D3-_8") (pintype "passive"))
    )
    (net (code "77") (name "/USB2D3_P") (class "Default")
      (node (ref "R28") (pin "2") (pinfunction "2_2") (pintype "passive"))
      (node (ref "U21") (pin "7") (pinfunction "USB2D3+_7") (pintype "passive"))
    )
    (net (code "78") (name "/USIM_CD") (class "Default")
      (node (ref "R35") (pin "2") (pinfunction "2_2") (pintype "passive"))
      (node (ref "U19") (pin "CD") (pinfunction "CD_CD") (pintype "passive"))
      (node (ref "U23") (pin "1") (pinfunction "CATHODE_1") (pintype "passive"))
      (node (ref "U25") (pin "44") (pinfunction "USIM_DET_44") (pintype "passive"))
    )
    (net (code "79") (name "/USIM_CLK") (class "Default")
      (node (ref "C69") (pin "2") (pinfunction "2_2") (pintype "passive"))
      (node (ref "R32") (pin "2") (pinfunction "2_2") (pintype "passive"))
      (node (ref "U19") (pin "C3") (pinfunction "CLK_C3") (pintype "passive"))
      (node (ref "U23") (pin "4") (pinfunction "CATHODE_4") (pintype "passive"))
    )
    (net (code "80") (name "/USIM_DATA") (class "Default")
      (node (ref "C68") (pin "2") (pinfunction "2_2") (pintype "passive"))
      (node (ref "R30") (pin "2") (pinfunction "2_2") (pintype "passive"))
      (node (ref "U19") (pin "C7") (pinfunction "I/O_C7") (pintype "passive"))
      (node (ref "U23") (pin "5") (pinfunction "CATHODE_5") (pintype "passive"))
    )
    (net (code "81") (name "/USIM_RST") (class "Default")
      (node (ref "C67") (pin "2") (pinfunction "2_2") (pintype "passive"))
      (node (ref "R33") (pin "2") (pinfunction "2_2") (pintype "passive"))
      (node (ref "U19") (pin "C2") (pinfunction "RST_C2") (pintype "passive"))
      (node (ref "U23") (pin "6") (pinfunction "CATHODE_6") (pintype "passive"))
    )
    (net (code "82") (name "/USIM_VDD") (class "Default")
      (node (ref "C66") (pin "2") (pinfunction "2_2") (pintype "passive"))
      (node (ref "U19") (pin "C1") (pinfunction "VCC_C1") (pintype "passive"))
      (node (ref "U23") (pin "3") (pinfunction "CATHODE_3") (pintype "passive"))
      (node (ref "U25") (pin "8") (pinfunction "USIM_VDD_8") (pintype "passive"))
    )
    (net (code "83") (name "/ZIGBEE_ANT") (class "Default")
      (node (ref "U33") (pin "1") (pinfunction "ANT_1") (pintype "passive"))
    )
    (net (code "84") (name "/ZIGBEE_LIG") (class "Default")
      (node (ref "R45") (pin "2") (pinfunction "2_2") (pintype "passive"))
      (node (ref "R46") (pin "2") (pinfunction "2_2") (pintype "passive"))
      (node (ref "U27") (pin "7") (pintype "passive"))
    )
    (net (code "85") (name "/ZIGBEE_RESET") (class "Default")
      (node (ref "R56") (pin "2") (pinfunction "2_2") (pintype "passive"))
      (node (ref "R57") (pin "2") (pinfunction "2_2") (pintype "passive"))
    )
    (net (code "86") (name "/ZIGBEE_SW") (class "Default")
      (node (ref "U32") (pin "6") (pinfunction "P1.7_6") (pintype "passive"))
    )
    (net (code "87") (name "GND") (class "Default")
      (node (ref "C35") (pin "1") (pinfunction "1_1") (pintype "passive"))
      (node (ref "C36") (pin "1") (pinfunction "1_1") (pintype "passive"))
      (node (ref "C37") (pin "1") (pinfunction "1_1") (pintype "passive"))
      (node (ref "C38") (pin "1") (pinfunction "1_1") (pintype "passive"))
      (node (ref "C39") (pin "1") (pinfunction "1_1") (pintype "passive"))
      (node (ref "C40") (pin "1") (pinfunction "1_1") (pintype "passive"))
      (node (ref "C41") (pin "1") (pinfunction "1_1") (pintype "passive"))
      (node (ref "C42") (pin "1") (pinfunction "1_1") (pintype "passive"))
      (node (ref "C43") (pin "1") (pinfunction "1_1") (pintype "passive"))
      (node (ref "C44") (pin "1") (pinfunction "1_1") (pintype "passive"))
      (node (ref "C45") (pin "1") (pinfunction "1_1") (pintype "passive"))
      (node (ref "C46") (pin "1") (pinfunction "1_1") (pintype "passive"))
      (node (ref "C47") (pin "1") (pinfunction "1_1") (pintype "passive"))
      (node (ref "C48") (pin "1") (pinfunction "1_1") (pintype "passive"))
      (node (ref "C49") (pin "1") (pinfunction "1_1") (pintype "passive"))
      (node (ref "C50") (pin "1") (pinfunction "1_1") (pintype "passive"))
      (node (ref "C51") (pin "1") (pinfunction "1_1") (pintype "passive"))
      (node (ref "C52") (pin "1") (pinfunction "1_1") (pintype "passive"))
      (node (ref "C53") (pin "1") (pinfunction "1_1") (pintype "passive"))
      (node (ref "C54") (pin "1") (pinfunction "1_1") (pintype "passive"))
      (node (ref "C55") (pin "1") (pinfunction "1_1") (pintype "passive"))
      (node (ref "C56") (pin "1") (pinfunction "1_1") (pintype "passive"))
      (node (ref "C57") (pin "2") (pinfunction "2_2") (pintype "passive"))
      (node (ref "C58") (pin "1") (pinfunction "1_1") (pintype "passive"))
      (node (ref "C59") (pin "1") (pinfunction "1_1") (pintype "passive"))
      (node (ref "C60") (pin "1") (pinfunction "1_1") (pintype "passive"))
      (node (ref "C61") (pin "1") (pinfunction "1_1") (pintype "passive"))
      (node (ref "C62") (pin "1") (pinfunction "1_1") (pintype "passive"))
      (node (ref "C63") (pin "1") (pinfunction "1_1") (pintype "passive"))
      (node (ref "C64") (pin "1") (pinfunction "1_1") (pintype "passive"))
      (node (ref "C65") (pin "1") (pinfunction "1_1") (pintype "passive"))
      (node (ref "C66") (pin "1") (pinfunction "1_1") (pintype "passive"))
      (node (ref "C67") (pin "1") (pinfunction "1_1") (pintype "passive"))
      (node (ref "C68") (pin "1") (pinfunction "1_1") (pintype "passive"))
      (node (ref "C69") (pin "1") (pinfunction "1_1") (pintype "passive"))
      (node (ref "C70") (pin "2") (pinfunction "2_2") (pintype "passive"))
      (node (ref "C73") (pin "1") (pinfunction "1_1") (pintype "passive"))
      (node (ref "C74") (pin "1") (pinfunction "1_1") (pintype "passive"))
      (node (ref "C75") (pin "1") (pinfunction "1_1") (pintype "passive"))
      (node (ref "C76") (pin "2") (pinfunction "2_2") (pintype "passive"))
      (node (ref "C77") (pin "2") (pinfunction "2_2") (pintype "passive"))
      (node (ref "C78") (pin "2") (pinfunction "2_2") (pintype "passive"))
      (node (ref "C79") (pin "2") (pinfunction "2_2") (pintype "passive"))
      (node (ref "C80") (pin "1") (pinfunction "1_1") (pintype "passive"))
      (node (ref "C81") (pin "1") (pinfunction "1_1") (pintype "passive"))
      (node (ref "C82") (pin "2") (pinfunction "2_2") (pintype "passive"))
      (node (ref "C83") (pin "2") (pinfunction "2_2") (pintype "passive"))
      (node (ref "C84") (pin "1") (pinfunction "1_1") (pintype "passive"))
      (node (ref "C85") (pin "1") (pinfunction "1_1") (pintype "passive"))
      (node (ref "C86") (pin "1") (pinfunction "1_1") (pintype "passive"))
      (node (ref "C87") (pin "1") (pinfunction "1_1") (pintype "passive"))
      (node (ref "C88") (pin "1") (pinfunction "1_1") (pintype "passive"))
      (node (ref "Q1") (pin "2") (pinfunction "E_2") (pintype "passive"))
      (node (ref "Q2") (pin "2") (pinfunction "E_2") (pintype "passive"))
      (node (ref "R18") (pin "1") (pinfunction "1_1") (pintype "passive"))
      (node (ref "R31") (pin "2") (pinfunction "2_2") (pintype "passive"))
      (node (ref "R34") (pin "2") (pinfunction "2_2") (pintype "passive"))
      (node (ref "R41") (pin "2") (pinfunction "2_2") (pintype "passive"))
      (node (ref "R54") (pin "1") (pinfunction "1_1") (pintype "passive"))
      (node (ref "R59") (pin "1") (pinfunction "1_1") (pintype "passive"))
      (node (ref "R61") (pin "2") (pinfunction "2_2") (pintype "passive"))
      (node (ref "U16") (pin "10") (pinfunction "MCT_10") (pintype "passive"))
      (node (ref "U16") (pin "S1") (pinfunction "SHIELD_S1") (pintype "passive"))
      (node (ref "U16") (pin "S2") (pinfunction "SHIELD_S2") (pintype "passive"))
      (node (ref "U17") (pin "2") (pinfunction "GND_2") (pintype "passive"))
      (node (ref "U17") (pin "3") (pinfunction "GND_3") (pintype "passive"))
      (node (ref "U17") (pin "4") (pinfunction "GND_4") (pintype "passive"))
      (node (ref "U18") (pin "2") (pinfunction "GND_2") (pintype "passive"))
      (node (ref "U18") (pin "4") (pinfunction "GND_4") (pintype "passive"))
      (node (ref "U19") (pin "1") (pinfunction "1_1") (pintype "passive"))
      (node (ref "U19") (pin "2") (pinfunction "2_2") (pintype "passive"))
      (node (ref "U19") (pin "3") (pinfunction "3_3") (pintype "passive"))
      (node (ref "U19") (pin "4") (pinfunction "4_4") (pintype "passive"))
      (node (ref "U19") (pin "C5") (pinfunction "GND_C5") (pintype "passive"))
      (node (ref "U20") (pin "2") (pinfunction "GND_2") (pintype "passive"))
      (node (ref "U20") (pin "3") (pinfunction "GND_3") (pintype "passive"))
      (node (ref "U20") (pin "4") (pinfunction "GND_4") (pintype "passive"))
      (node (ref "U21") (pin "0") (pinfunction "EPAD_0") (pintype "passive"))
      (node (ref "U22") (pin "11") (pinfunction "TMDSClockSchield_11") (pintype "passive"))
      (node (ref "U22") (pin "17") (pinfunction "DDC/CECGround_17") (pintype "passive"))
      (node (ref "U22") (pin "2") (pinfunction "TMDSData2Shield_2") (pintype "passive"))
      (node (ref "U22") (pin "5") (pinfunction "TMDSData1Shield_5") (pintype "passive"))
      (node (ref "U22") (pin "8") (pinfunction "TMDSData0Shield_8") (pintype "passive"))
      (node (ref "U22") (pin "S1") (pinfunction "S_S1") (pintype "passive"))
      (node (ref "U22") (pin "S2") (pinfunction "S_S2") (pintype "passive"))
      (node (ref "U22") (pin "S3") (pinfunction "S_S3") (pintype "passive"))
      (node (ref "U22") (pin "S4") (pinfunction "S_S4") (pintype "passive"))
      (node (ref "U23") (pin "2") (pinfunction "ANODE_2") (pintype "passive"))
      (node (ref "U24") (pin "15") (pinfunction "GND_15") (pintype "passive"))
      (node (ref "U24") (pin "18") (pinfunction "GND_18") (pintype "passive"))
      (node (ref "U24") (pin "21") (pinfunction "GND_21") (pintype "passive"))
      (node (ref "U24") (pin "26") (pinfunction "GND_26") (pintype "passive"))
      (node (ref "U24") (pin "27") (pinfunction "GND_27") (pintype "passive"))
      (node (ref "U24") (pin "29") (pinfunction "GND_29") (pintype "passive"))
      (node (ref "U24") (pin "34") (pinfunction "GND_34") (pintype "passive"))
      (node (ref "U24") (pin "35") (pinfunction "GND_35") (pintype "passive"))
      (node (ref "U24") (pin "37") (pinfunction "GND_37") (pintype "passive"))
      (node (ref "U24") (pin "4") (pinfunction "GND_4") (pintype "passive"))
      (node (ref "U24") (pin "40") (pinfunction "GND_40") (pintype "passive"))
      (node (ref "U24") (pin "43") (pinfunction "GND_43") (pintype "passive"))
      (node (ref "U24") (pin "50") (pinfunction "GND_50") (pintype "passive"))
      (node (ref "U24") (pin "53") (pinfunction "53_53") (pintype "passive"))
      (node (ref "U24") (pin "54") (pinfunction "54_54") (pintype "passive"))
      (node (ref "U24") (pin "55") (pinfunction "55_55") (pintype "passive"))
      (node (ref "U24") (pin "56") (pinfunction "56_56") (pintype "passive"))
      (node (ref "U24") (pin "9") (pinfunction "GND_9") (pintype "passive"))
      (node (ref "U25") (pin "15") (pinfunction "GND_15") (pintype "passive"))
      (node (ref "U25") (pin "18") (pinfunction "GND_18") (pintype "passive"))
      (node (ref "U25") (pin "21") (pinfunction "GND_21") (pintype "passive"))
      (node (ref "U25") (pin "26") (pinfunction "GND_26") (pintype "passive"))
      (node (ref "U25") (pin "27") (pinfunction "GND_27") (pintype "passive"))
      (node (ref "U25") (pin "29") (pinfunction "GND_29") (pintype "passive"))
      (node (ref "U25") (pin "34") (pinfunction "GND_34") (pintype "passive"))
      (node (ref "U25") (pin "35") (pinfunction "GND_35") (pintype "passive"))
      (node (ref "U25") (pin "37") (pinfunction "GND_37") (pintype "passive"))
      (node (ref "U25") (pin "4") (pinfunction "GND_4") (pintype "passive"))
      (node (ref "U25") (pin "40") (pinfunction "GND_40") (pintype "passive"))
      (node (ref "U25") (pin "43") (pinfunction "GND_43") (pintype "passive"))
      (node (ref "U25") (pin "50") (pinfunction "GND_50") (pintype "passive"))
      (node (ref "U25") (pin "53") (pinfunction "53_53") (pintype "passive"))
      (node (ref "U25") (pin "54") (pinfunction "54_54") (pintype "passive"))
      (node (ref "U25") (pin "55") (pinfunction "55_55") (pintype "passive"))
      (node (ref "U25") (pin "56") (pinfunction "56_56") (pintype "passive"))
      (node (ref "U25") (pin "9") (pinfunction "GND_9") (pintype "passive"))
      (node (ref "U26") (pin "1") (pinfunction "GND_1") (pintype "passive"))
      (node (ref "U26") (pin "12") (pinfunction "GND_12") (pintype "passive"))
      (node (ref "U26") (pin "14") (pinfunction "GND_14") (pintype "passive"))
      (node (ref "U26") (pin "15") (pinfunction "GND_15") (pintype "passive"))
      (node (ref "U26") (pin "16") (pinfunction "GND_16") (pintype "passive"))
      (node (ref "U27") (pin "2") (pintype "passive"))
      (node (ref "U27") (pin "6") (pintype "passive"))
      (node (ref "U27") (pin "8") (pintype "passive"))
      (node (ref "U28") (pin "1") (pinfunction "GND_1") (pintype "passive"))
      (node (ref "U28") (pin "10") (pinfunction "GND_10") (pintype "passive"))
      (node (ref "U28") (pin "12") (pinfunction "GND_12") (pintype "passive"))
      (node (ref "U29") (pin "5") (pinfunction "GND_5") (pintype "passive"))
      (node (ref "U31") (pin "3") (pintype "passive"))
      (node (ref "U32") (pin "1") (pinfunction "GND_1") (pintype "passive"))
      (node (ref "U33") (pin "2") (pinfunction "GND_2") (pintype "passive"))
      (node (ref "U33") (pin "3") (pinfunction "GND_3") (pintype "passive"))
      (node (ref "U33") (pin "4") (pinfunction "GND_4") (pintype "passive"))
      (node (ref "U34") (pin "2") (pinfunction "GND_2") (pintype "passive"))
      (node (ref "U36") (pin "3") (pintype "passive"))
    )
    (net (code "88") (name "Net-(C35-Pad2)") (class "Default")
      (node (ref "C35") (pin "2") (pinfunction "2_2") (pintype "passive"))
      (node (ref "U16") (pin "1") (pinfunction "MCT_1") (pintype "passive"))
    )
    (net (code "89") (name "Net-(C88-Pad2)") (class "Default")
      (node (ref "C88") (pin "2") (pinfunction "2_2") (pintype "passive"))
      (node (ref "R63") (pin "1") (pinfunction "1_1") (pintype "passive"))
      (node (ref "R64") (pin "1") (pinfunction "1_1") (pintype "passive"))
    )
    (net (code "90") (name "Net-(L4-Pad1)") (class "Default")
      (node (ref "L4") (pin "1") (pinfunction "1_1") (pintype "passive"))
      (node (ref "R52") (pin "2") (pinfunction "2_2") (pintype "passive"))
    )
    (net (code "91") (name "Net-(Q1-B)") (class "Default")
      (node (ref "Q1") (pin "1") (pinfunction "B_1") (pintype "passive"))
      (node (ref "R17") (pin "2") (pinfunction "2_2") (pintype "passive"))
      (node (ref "R18") (pin "2") (pinfunction "2_2") (pintype "passive"))
    )
    (net (code "92") (name "Net-(Q1-C)") (class "Default")
      (node (ref "Q1") (pin "3") (pinfunction "C_3") (pintype "passive"))
      (node (ref "U25") (pin "22") (pinfunction "PESRT1#_22") (pintype "passive"))
    )
    (net (code "93") (name "Net-(Q2-B)") (class "Default")
      (node (ref "Q2") (pin "1") (pinfunction "B_1") (pintype "passive"))
      (node (ref "R58") (pin "2") (pinfunction "2_2") (pintype "passive"))
      (node (ref "R59") (pin "2") (pinfunction "2_2") (pintype "passive"))
    )
    (net (code "94") (name "Net-(Q2-C)") (class "Default")
      (node (ref "Q2") (pin "3") (pinfunction "C_3") (pintype "passive"))
      (node (ref "U28") (pin "9") (pinfunction "RESET_9") (pintype "passive"))
    )
    (net (code "95") (name "Net-(R20-Pad2)") (class "Default")
      (node (ref "R20") (pin "2") (pinfunction "2_2") (pintype "passive"))
      (node (ref "U16") (pin "11") (pinfunction "11_11") (pintype "passive"))
    )
    (net (code "96") (name "Net-(R23-Pad2)") (class "Default")
      (node (ref "R23") (pin "2") (pinfunction "2_2") (pintype "passive"))
      (node (ref "U16") (pin "14") (pinfunction "14_14") (pintype "passive"))
    )
    (net (code "97") (name "Net-(R24-Pad2)") (class "Default")
      (node (ref "R24") (pin "2") (pinfunction "2_2") (pintype "passive"))
      (node (ref "R25") (pin "2") (pinfunction "2_2") (pintype "passive"))
      (node (ref "R26") (pin "2") (pinfunction "2_2") (pintype "passive"))
      (node (ref "R27") (pin "2") (pinfunction "2_2") (pintype "passive"))
    )
    (net (code "98") (name "Net-(U21-PEXWAKE#)") (class "Default")
      (node (ref "R38") (pin "1") (pinfunction "1_1") (pintype "passive"))
      (node (ref "U21") (pin "20") (pinfunction "PEXWAKE#_20") (pintype "passive"))
    )
    (net (code "99") (name "Net-(U21-SMI#)") (class "Default")
      (node (ref "R39") (pin "1") (pinfunction "1_1") (pintype "passive"))
      (node (ref "U21") (pin "18") (pinfunction "SMI#_18") (pintype "passive"))
    )
    (net (code "100") (name "Net-(U21-SSREXT)") (class "Default")
      (node (ref "R31") (pin "1") (pinfunction "1_1") (pintype "passive"))
      (node (ref "U21") (pin "50") (pinfunction "SSREXT_50") (pintype "passive"))
    )
    (net (code "101") (name "Net-(U21-TESTEN)") (class "Default")
      (node (ref "R34") (pin "1") (pinfunction "1_1") (pintype "passive"))
      (node (ref "U21") (pin "51") (pinfunction "TESTEN_51") (pintype "passive"))
    )
    (net (code "102") (name "Net-(U21-USBHOC1#)") (class "Default")
      (node (ref "R24") (pin "1") (pinfunction "1_1") (pintype "passive"))
      (node (ref "U21") (pin "43") (pinfunction "USBHOC1#_43") (pintype "passive"))
    )
    (net (code "103") (name "Net-(U21-USBHOC2#)") (class "Default")
      (node (ref "R25") (pin "1") (pinfunction "1_1") (pintype "passive"))
      (node (ref "U21") (pin "41") (pinfunction "USBHOC2#_41") (pintype "passive"))
    )
    (net (code "104") (name "Net-(U21-USBHOC3#)") (class "Default")
      (node (ref "R26") (pin "1") (pinfunction "1_1") (pintype "passive"))
      (node (ref "U21") (pin "39") (pinfunction "USBHOC3#_39") (pintype "passive"))
    )
    (net (code "105") (name "Net-(U21-USBHOC4#)") (class "Default")
      (node (ref "R27") (pin "1") (pinfunction "1_1") (pintype "passive"))
      (node (ref "U21") (pin "37") (pinfunction "USBHOC4#_37") (pintype "passive"))
    )
    (net (code "106") (name "Net-(U24-MIC_N)") (class "Default")
      (node (ref "R36") (pin "1") (pinfunction "1_1") (pintype "passive"))
      (node (ref "U24") (pin "3") (pinfunction "MIC_N_3") (pintype "passive"))
    )
    (net (code "107") (name "Net-(U24-PESRT1#)") (class "Default")
      (node (ref "R19") (pin "2") (pinfunction "2_2") (pintype "passive"))
      (node (ref "U24") (pin "22") (pinfunction "PESRT1#_22") (pintype "passive"))
    )
    (net (code "108") (name "Net-(U25-LED_WWAN#)") (class "Default")
      (node (ref "R21") (pin "1") (pinfunction "1_1") (pintype "passive"))
      (node (ref "U25") (pin "42") (pinfunction "LED_WWAN#_42") (pintype "passive"))
    )
    (net (code "109") (name "Net-(U25-USB_DM)") (class "Default")
      (node (ref "R22") (pin "2") (pinfunction "2_2") (pintype "passive"))
      (node (ref "U25") (pin "36") (pinfunction "USB_DM_36") (pintype "passive"))
    )
    (net (code "110") (name "Net-(U25-USB_DP)") (class "Default")
      (node (ref "R28") (pin "1") (pinfunction "1_1") (pintype "passive"))
      (node (ref "U25") (pin "38") (pinfunction "USB_DP_38") (pintype "passive"))
    )
    (net (code "111") (name "Net-(U25-USIM_CLK)") (class "Default")
      (node (ref "R32") (pin "1") (pinfunction "1_1") (pintype "passive"))
      (node (ref "U25") (pin "12") (pinfunction "USIM_CLK_12") (pintype "passive"))
    )
    (net (code "112") (name "Net-(U25-USIM_DATA)") (class "Default")
      (node (ref "R30") (pin "1") (pinfunction "1_1") (pintype "passive"))
      (node (ref "U25") (pin "10") (pinfunction "USIM_DATA_10") (pintype "passive"))
    )
    (net (code "113") (name "Net-(U25-USIM_RST)") (class "Default")
      (node (ref "R33") (pin "1") (pinfunction "1_1") (pintype "passive"))
      (node (ref "U25") (pin "14") (pinfunction "USIM_RST_14") (pintype "passive"))
    )
    (net (code "114") (name "Net-(U26-GD00)") (class "Default")
      (node (ref "R40") (pin "2") (pinfunction "2_2") (pintype "passive"))
      (node (ref "U26") (pin "6") (pinfunction "GD00_6") (pintype "passive"))
    )
    (net (code "115") (name "Net-(U28-RF_IN)") (class "Default")
      (node (ref "R55") (pin "1") (pinfunction "1_1") (pintype "passive"))
      (node (ref "U28") (pin "11") (pinfunction "RF_IN_11") (pintype "passive"))
    )
    (net (code "116") (name "Net-(U28-RXD1)") (class "Default")
      (node (ref "R47") (pin "2") (pinfunction "2_2") (pintype "passive"))
      (node (ref "U28") (pin "3") (pinfunction "RXD1_3") (pintype "passive"))
    )
    (net (code "117") (name "Net-(U28-STANDBY)") (class "Default")
      (node (ref "R49") (pin "2") (pinfunction "2_2") (pintype "passive"))
      (node (ref "U28") (pin "5") (pinfunction "STANDBY_5") (pintype "passive"))
    )
    (net (code "118") (name "Net-(U28-TIMER)") (class "Default")
      (node (ref "R41") (pin "1") (pinfunction "1_1") (pintype "passive"))
      (node (ref "U28") (pin "18") (pinfunction "TIMER_18") (pintype "passive"))
    )
    (net (code "119") (name "Net-(U28-TXD1)") (class "Default")
      (node (ref "R44") (pin "2") (pinfunction "2_2") (pintype "passive"))
      (node (ref "U28") (pin "2") (pinfunction "TXD1_2") (pintype "passive"))
    )
    (net (code "120") (name "Net-(U28-VCC_RF)") (class "Default")
      (node (ref "R52") (pin "1") (pinfunction "1_1") (pintype "passive"))
      (node (ref "U28") (pin "14") (pinfunction "VCC_RF_14") (pintype "passive"))
    )
    (net (code "121") (name "Net-(U28-V_BCKP)") (class "Default")
      (node (ref "R53") (pin "2") (pinfunction "2_2") (pintype "passive"))
      (node (ref "U28") (pin "6") (pinfunction "V_BCKP_6") (pintype "passive"))
    )
    (net (code "122") (name "Net-(U29-A)") (class "Default")
      (node (ref "R50") (pin "2") (pinfunction "2_2") (pintype "passive"))
      (node (ref "R51") (pin "2") (pinfunction "2_2") (pintype "passive"))
      (node (ref "U29") (pin "6") (pinfunction "A_6") (pintype "passive"))
      (node (ref "U30") (pin "2") (pinfunction "A_2") (pintype "passive"))
      (node (ref "U31") (pin "1") (pintype "passive"))
    )
    (net (code "123") (name "Net-(U29-B)") (class "Default")
      (node (ref "R50") (pin "1") (pinfunction "1_1") (pintype "passive"))
      (node (ref "U29") (pin "7") (pinfunction "B_7") (pintype "passive"))
      (node (ref "U30") (pin "1") (pinfunction "B_1") (pintype "passive"))
      (node (ref "U31") (pin "2") (pintype "passive"))
    )
    (net (code "124") (name "Net-(U29-DI)") (class "Default")
      (node (ref "R48") (pin "2") (pinfunction "2_2") (pintype "passive"))
      (node (ref "U29") (pin "4") (pinfunction "DI_4") (pintype "passive"))
    )
    (net (code "125") (name "Net-(U29-RO)") (class "Default")
      (node (ref "R42") (pin "2") (pinfunction "2_2") (pintype "passive"))
      (node (ref "U29") (pin "1") (pinfunction "RO_1") (pintype "passive"))
    )
    (net (code "126") (name "Net-(U29-VCC)") (class "Default")
      (node (ref "C78") (pin "1") (pinfunction "1_1") (pintype "passive"))
      (node (ref "C79") (pin "1") (pinfunction "1_1") (pintype "passive"))
      (node (ref "R43") (pin "1") (pinfunction "1_1") (pintype "passive"))
      (node (ref "U29") (pin "8") (pinfunction "VCC_8") (pintype "passive"))
    )
    (net (code "127") (name "Net-(U32-P1.2)") (class "Default")
      (node (ref "R46") (pin "1") (pinfunction "1_1") (pintype "passive"))
      (node (ref "U32") (pin "13") (pinfunction "P1.2_13") (pintype "passive"))
    )
    (net (code "128") (name "Net-(U32-P1.3)") (class "Default")
      (node (ref "R45") (pin "1") (pinfunction "1_1") (pintype "passive"))
      (node (ref "U32") (pin "12") (pinfunction "P1.3_12") (pintype "passive"))
    )
    (net (code "129") (name "Net-(U32-RESET)") (class "Default")
      (node (ref "R57") (pin "1") (pinfunction "1_1") (pintype "passive"))
      (node (ref "U32") (pin "24") (pinfunction "RESET_24") (pintype "passive"))
    )
    (net (code "130") (name "Net-(U34-CANH)") (class "Default")
      (node (ref "R63") (pin "2") (pinfunction "2_2") (pintype "passive"))
      (node (ref "U34") (pin "7") (pinfunction "CANH_7") (pintype "passive"))
      (node (ref "U35") (pin "1") (pinfunction "B_1") (pintype "passive"))
      (node (ref "U36") (pin "2") (pintype "passive"))
    )
    (net (code "131") (name "Net-(U34-CANL)") (class "Default")
      (node (ref "R64") (pin "2") (pinfunction "2_2") (pintype "passive"))
      (node (ref "U34") (pin "6") (pinfunction "CANL_6") (pintype "passive"))
      (node (ref "U35") (pin "2") (pinfunction "A_2") (pintype "passive"))
      (node (ref "U36") (pin "1") (pintype "passive"))
    )
    (net (code "132") (name "Net-(U34-RXD)") (class "Default")
      (node (ref "R62") (pin "2") (pinfunction "2_2") (pintype "passive"))
      (node (ref "U34") (pin "4") (pinfunction "RXD_4") (pintype "passive"))
    )
    (net (code "133") (name "Net-(U34-STB)") (class "Default")
      (node (ref "R61") (pin "1") (pinfunction "1_1") (pintype "passive"))
      (node (ref "U34") (pin "8") (pinfunction "STB_8") (pintype "passive"))
    )
    (net (code "134") (name "Net-(U34-TXD)") (class "Default")
      (node (ref "R60") (pin "2") (pinfunction "2_2") (pintype "passive"))
      (node (ref "U34") (pin "1") (pinfunction "TXD_1") (pintype "passive"))
    )
    (net (code "135") (name "PWR_1V05") (class "Default")
      (node (ref "C58") (pin "2") (pinfunction "2_2") (pintype "passive"))
      (node (ref "C59") (pin "2") (pinfunction "2_2") (pintype "passive"))
      (node (ref "C60") (pin "2") (pinfunction "2_2") (pintype "passive"))
      (node (ref "C61") (pin "2") (pinfunction "2_2") (pintype "passive"))
      (node (ref "C62") (pin "2") (pinfunction "2_2") (pintype "passive"))
      (node (ref "C63") (pin "2") (pinfunction "2_2") (pintype "passive"))
      (node (ref "C64") (pin "2") (pinfunction "2_2") (pintype "passive"))
      (node (ref "C65") (pin "2") (pinfunction "2_2") (pintype "passive"))
      (node (ref "U21") (pin "12") (pinfunction "VCCA10SSRX34_12") (pintype "passive"))
      (node (ref "U21") (pin "29") (pinfunction "VDD_29") (pintype "passive"))
      (node (ref "U21") (pin "3") (pinfunction "VCCA10SSRX34_3") (pintype "passive"))
      (node (ref "U21") (pin "45") (pinfunction "VDD_45") (pintype "passive"))
      (node (ref "U21") (pin "54") (pinfunction "VCCA10SSRX12_54") (pintype "passive"))
      (node (ref "U21") (pin "60") (pinfunction "VDD_60") (pintype "passive"))
      (node (ref "U21") (pin "63") (pinfunction "VCCA10SSRX12_63") (pintype "passive"))
      (node (ref "U21") (pin "9") (pinfunction "VDD_9") (pintype "passive"))
    )
    (net (code "136") (name "PWR_3V3") (class "Default")
      (node (ref "C42") (pin "2") (pinfunction "2_2") (pintype "passive"))
      (node (ref "C43") (pin "2") (pinfunction "2_2") (pintype "passive"))
      (node (ref "C44") (pin "2") (pinfunction "2_2") (pintype "passive"))
      (node (ref "C45") (pin "2") (pinfunction "2_2") (pintype "passive"))
      (node (ref "C46") (pin "2") (pinfunction "2_2") (pintype "passive"))
      (node (ref "C47") (pin "2") (pinfunction "2_2") (pintype "passive"))
      (node (ref "C48") (pin "2") (pinfunction "2_2") (pintype "passive"))
      (node (ref "C49") (pin "2") (pinfunction "2_2") (pintype "passive"))
      (node (ref "C50") (pin "2") (pinfunction "2_2") (pintype "passive"))
      (node (ref "C51") (pin "2") (pinfunction "2_2") (pintype "passive"))
      (node (ref "C52") (pin "2") (pinfunction "2_2") (pintype "passive"))
      (node (ref "C53") (pin "2") (pinfunction "2_2") (pintype "passive"))
      (node (ref "C54") (pin "2") (pinfunction "2_2") (pintype "passive"))
      (node (ref "C55") (pin "2") (pinfunction "2_2") (pintype "passive"))
      (node (ref "C76") (pin "1") (pinfunction "1_1") (pintype "passive"))
      (node (ref "C77") (pin "1") (pinfunction "1_1") (pintype "passive"))
      (node (ref "C80") (pin "2") (pinfunction "2_2") (pintype "passive"))
      (node (ref "C81") (pin "2") (pinfunction "2_2") (pintype "passive"))
      (node (ref "C82") (pin "1") (pinfunction "1_1") (pintype "passive"))
      (node (ref "C83") (pin "1") (pinfunction "1_1") (pintype "passive"))
      (node (ref "C84") (pin "2") (pinfunction "2_2") (pintype "passive"))
      (node (ref "C85") (pin "2") (pinfunction "2_2") (pintype "passive"))
      (node (ref "D4") (pin "1") (pinfunction "K_1") (pintype "passive"))
      (node (ref "R20") (pin "1") (pinfunction "1_1") (pintype "passive"))
      (node (ref "R23") (pin "1") (pinfunction "1_1") (pintype "passive"))
      (node (ref "R29") (pin "2") (pinfunction "2_2") (pintype "passive"))
      (node (ref "R37") (pin "2") (pinfunction "2_2") (pintype "passive"))
      (node (ref "R38") (pin "2") (pinfunction "2_2") (pintype "passive"))
      (node (ref "R39") (pin "2") (pinfunction "2_2") (pintype "passive"))
      (node (ref "R43") (pin "2") (pinfunction "2_2") (pintype "passive"))
      (node (ref "R49") (pin "1") (pinfunction "1_1") (pintype "passive"))
      (node (ref "R51") (pin "1") (pinfunction "1_1") (pintype "passive"))
      (node (ref "R53") (pin "1") (pinfunction "1_1") (pintype "passive"))
      (node (ref "R56") (pin "1") (pinfunction "1_1") (pintype "passive"))
      (node (ref "U21") (pin "15") (pinfunction "VCCA33SS34_15") (pintype "passive"))
      (node (ref "U21") (pin "23") (pinfunction "VCCA33PEX_23") (pintype "passive"))
      (node (ref "U21") (pin "32") (pinfunction "VSU33_32") (pintype "passive"))
      (node (ref "U21") (pin "46") (pinfunction "VSUS33_46") (pintype "passive"))
      (node (ref "U21") (pin "49") (pinfunction "VCCA33SSM_49") (pintype "passive"))
      (node (ref "U21") (pin "57") (pinfunction "VCCA33SS12_57") (pintype "passive"))
      (node (ref "U21") (pin "6") (pinfunction "VCCA33SS34_6") (pintype "passive"))
      (node (ref "U21") (pin "66") (pinfunction "VCCA33SS12_66") (pintype "passive"))
      (node (ref "U24") (pin "2") (pinfunction "VCC_2") (pintype "passive"))
      (node (ref "U24") (pin "24") (pinfunction "VCC_24") (pintype "passive"))
      (node (ref "U24") (pin "39") (pinfunction "VCC_39") (pintype "passive"))
      (node (ref "U24") (pin "41") (pinfunction "VCC_41") (pintype "passive"))
      (node (ref "U24") (pin "52") (pinfunction "VCC_52") (pintype "passive"))
      (node (ref "U26") (pin "11") (pinfunction "VCC_11") (pintype "passive"))
      (node (ref "U27") (pin "3") (pintype "passive"))
      (node (ref "U28") (pin "8") (pinfunction "VCC_8") (pintype "passive"))
      (node (ref "U32") (pin "2") (pinfunction "VCC_2") (pintype "passive"))
      (node (ref "U34") (pin "5") (pinfunction "VIO_5") (pintype "passive"))
    )
    (net (code "137") (name "PWR_3V4") (class "Default")
      (node (ref "C36") (pin "2") (pinfunction "2_2") (pintype "passive"))
      (node (ref "C37") (pin "2") (pinfunction "2_2") (pintype "passive"))
      (node (ref "C38") (pin "2") (pinfunction "2_2") (pintype "passive"))
      (node (ref "C39") (pin "2") (pinfunction "2_2") (pintype "passive"))
      (node (ref "C40") (pin "2") (pinfunction "2_2") (pintype "passive"))
      (node (ref "C41") (pin "2") (pinfunction "2_2") (pintype "passive"))
      (node (ref "U25") (pin "2") (pinfunction "VCC_2") (pintype "passive"))
      (node (ref "U25") (pin "24") (pinfunction "VCC_24") (pintype "passive"))
      (node (ref "U25") (pin "39") (pinfunction "VCC_39") (pintype "passive"))
      (node (ref "U25") (pin "41") (pinfunction "VCC_41") (pintype "passive"))
      (node (ref "U25") (pin "52") (pinfunction "VCC_52") (pintype "passive"))
    )
    (net (code "138") (name "PWR_5V") (class "Default")
      (node (ref "C74") (pin "2") (pinfunction "2_2") (pintype "passive"))
      (node (ref "C75") (pin "2") (pinfunction "2_2") (pintype "passive"))
      (node (ref "C86") (pin "2") (pinfunction "2_2") (pintype "passive"))
      (node (ref "C87") (pin "2") (pinfunction "2_2") (pintype "passive"))
      (node (ref "U22") (pin "18") (pinfunction "+5V_18") (pintype "passive"))
      (node (ref "U34") (pin "3") (pinfunction "VCC_3") (pintype "passive"))
    )
    (net (code "139") (name "VDD_EXT") (class "Default")
      (node (ref "R35") (pin "1") (pinfunction "1_1") (pintype "passive"))
      (node (ref "U25") (pin "11") (pinfunction "VDD_EXT_11") (pintype "passive"))
    )
    (net (code "140") (name "unconnected-(U19-VPP-PadC6)") (class "Default")
      (node (ref "U19") (pin "C6") (pinfunction "VPP_C6") (pintype "passive+no_connect"))
    )
    (net (code "141") (name "unconnected-(U21-NC-Pad26)") (class "Default")
      (node (ref "U21") (pin "26") (pinfunction "NC_26") (pintype "passive+no_connect"))
    )
    (net (code "142") (name "unconnected-(U21-SPICK-Pad35)") (class "Default")
      (node (ref "U21") (pin "35") (pinfunction "SPICK_35") (pintype "passive+no_connect"))
    )
    (net (code "143") (name "unconnected-(U21-SPICS#-Pad34)") (class "Default")
      (node (ref "U21") (pin "34") (pinfunction "SPICS#_34") (pintype "passive+no_connect"))
    )
    (net (code "144") (name "unconnected-(U21-SPISI-Pad36)") (class "Default")
      (node (ref "U21") (pin "36") (pinfunction "SPISI_36") (pintype "passive+no_connect"))
    )
    (net (code "145") (name "unconnected-(U21-SPISO-Pad33)") (class "Default")
      (node (ref "U21") (pin "33") (pinfunction "SPISO_33") (pintype "passive+no_connect"))
    )
    (net (code "146") (name "unconnected-(U21-SSRX3+-Pad4)") (class "Default")
      (node (ref "U21") (pin "4") (pinfunction "SSRX3+_4") (pintype "passive+no_connect"))
    )
    (net (code "147") (name "unconnected-(U21-SSRX3--Pad5)") (class "Default")
      (node (ref "U21") (pin "5") (pinfunction "SSRX3-_5") (pintype "passive+no_connect"))
    )
    (net (code "148") (name "unconnected-(U21-SSRX4+-Pad13)") (class "Default")
      (node (ref "U21") (pin "13") (pinfunction "SSRX4+_13") (pintype "passive+no_connect"))
    )
    (net (code "149") (name "unconnected-(U21-SSRX4--Pad14)") (class "Default")
      (node (ref "U21") (pin "14") (pinfunction "SSRX4-_14") (pintype "passive+no_connect"))
    )
    (net (code "150") (name "unconnected-(U21-SSTX3+-Pad1)") (class "Default")
      (node (ref "U21") (pin "1") (pinfunction "SSTX3+_1") (pintype "passive+no_connect"))
    )
    (net (code "151") (name "unconnected-(U21-SSTX3--Pad2)") (class "Default")
      (node (ref "U21") (pin "2") (pinfunction "SSTX3-_2") (pintype "passive+no_connect"))
    )
    (net (code "152") (name "unconnected-(U21-SSTX4+-Pad10)") (class "Default")
      (node (ref "U21") (pin "10") (pinfunction "SSTX4+_10") (pintype "passive+no_connect"))
    )
    (net (code "153") (name "unconnected-(U21-SSTX4--Pad11)") (class "Default")
      (node (ref "U21") (pin "11") (pinfunction "SSTX4-_11") (pintype "passive+no_connect"))
    )
    (net (code "154") (name "unconnected-(U21-USB2D4+-Pad16)") (class "Default")
      (node (ref "U21") (pin "16") (pinfunction "USB2D4+_16") (pintype "passive+no_connect"))
    )
    (net (code "155") (name "unconnected-(U21-USB2D4--Pad17)") (class "Default")
      (node (ref "U21") (pin "17") (pinfunction "USB2D4-_17") (pintype "passive+no_connect"))
    )
    (net (code "156") (name "unconnected-(U21-USBHPE1#-Pad44)") (class "Default")
      (node (ref "U21") (pin "44") (pinfunction "USBHPE1#_44") (pintype "passive+no_connect"))
    )
    (net (code "157") (name "unconnected-(U21-USBHPE2#-Pad42)") (class "Default")
      (node (ref "U21") (pin "42") (pinfunction "USBHPE2#_42") (pintype "passive+no_connect"))
    )
    (net (code "158") (name "unconnected-(U21-USBHPE3#-Pad40)") (class "Default")
      (node (ref "U21") (pin "40") (pinfunction "USBHPE3#_40") (pintype "passive+no_connect"))
    )
    (net (code "159") (name "unconnected-(U21-USBHPE4#-Pad38)") (class "Default")
      (node (ref "U21") (pin "38") (pinfunction "USBHPE4#_38") (pintype "passive+no_connect"))
    )
    (net (code "160") (name "unconnected-(U22-Reserved-Pad14)") (class "Default")
      (node (ref "U22") (pin "14") (pinfunction "Reserved_14") (pintype "passive+no_connect"))
    )
    (net (code "161") (name "unconnected-(U24-LED_WWAN#-Pad42)") (class "Default")
      (node (ref "U24") (pin "42") (pinfunction "LED_WWAN#_42") (pintype "passive+no_connect"))
    )
    (net (code "162") (name "unconnected-(U24-MIC_P-Pad1)") (class "Default")
      (node (ref "U24") (pin "1") (pinfunction "MIC_P_1") (pintype "passive+no_connect"))
    )
    (net (code "163") (name "unconnected-(U24-NC1-Pad6)") (class "Default")
      (node (ref "U24") (pin "6") (pinfunction "NC1_6") (pintype "passive+no_connect"))
    )
    (net (code "164") (name "unconnected-(U24-NC2-Pad48)") (class "Default")
      (node (ref "U24") (pin "48") (pinfunction "NC2_48") (pintype "passive+no_connect"))
    )
    (net (code "165") (name "unconnected-(U24-PESRT2#-Pad33)") (class "Default")
      (node (ref "U24") (pin "33") (pinfunction "PESRT2#_33") (pintype "passive+no_connect"))
    )
    (net (code "166") (name "unconnected-(U24-RESERVED1-Pad13)") (class "Default")
      (node (ref "U24") (pin "13") (pinfunction "RESERVED1_13") (pintype "passive+no_connect"))
    )
    (net (code "167") (name "unconnected-(U24-RESERVED2-Pad16)") (class "Default")
      (node (ref "U24") (pin "16") (pinfunction "RESERVED2_16") (pintype "passive+no_connect"))
    )
    (net (code "168") (name "unconnected-(U24-RESERVED3-Pad17)") (class "Default")
      (node (ref "U24") (pin "17") (pinfunction "RESERVED3_17") (pintype "passive+no_connect"))
    )
    (net (code "169") (name "unconnected-(U24-SPK_N-Pad7)") (class "Default")
      (node (ref "U24") (pin "7") (pinfunction "SPK_N_7") (pintype "passive+no_connect"))
    )
    (net (code "170") (name "unconnected-(U24-SPK_P-Pad5)") (class "Default")
      (node (ref "U24") (pin "5") (pinfunction "SPK_P_5") (pintype "passive+no_connect"))
    )
    (net (code "171") (name "unconnected-(U24-UART_CTS-Pad28)") (class "Default")
      (node (ref "U24") (pin "28") (pinfunction "UART_CTS_28") (pintype "passive+no_connect"))
    )
    (net (code "172") (name "unconnected-(U24-UART_DCD-Pad30)") (class "Default")
      (node (ref "U24") (pin "30") (pinfunction "UART_DCD_30") (pintype "passive+no_connect"))
    )
    (net (code "173") (name "unconnected-(U24-UART_DTR-Pad46)") (class "Default")
      (node (ref "U24") (pin "46") (pinfunction "UART_DTR_46") (pintype "passive+no_connect"))
    )
    (net (code "174") (name "unconnected-(U24-UART_RTS-Pad25)") (class "Default")
      (node (ref "U24") (pin "25") (pinfunction "UART_RTS_25") (pintype "passive+no_connect"))
    )
    (net (code "175") (name "unconnected-(U24-UART_RXD-Pad23)") (class "Default")
      (node (ref "U24") (pin "23") (pinfunction "UART_RXD_23") (pintype "passive+no_connect"))
    )
    (net (code "176") (name "unconnected-(U24-UART_TXD-Pad31)") (class "Default")
      (node (ref "U24") (pin "31") (pinfunction "UART_TXD_31") (pintype "passive+no_connect"))
    )
    (net (code "177") (name "unconnected-(U24-USB_DM-Pad36)") (class "Default")
      (node (ref "U24") (pin "36") (pinfunction "USB_DM_36") (pintype "passive+no_connect"))
    )
    (net (code "178") (name "unconnected-(U24-USB_DP-Pad38)") (class "Default")
      (node (ref "U24") (pin "38") (pinfunction "USB_DP_38") (pintype "passive+no_connect"))
    )
    (net (code "179") (name "unconnected-(U24-USIM_CLK-Pad12)") (class "Default")
      (node (ref "U24") (pin "12") (pinfunction "USIM_CLK_12") (pintype "passive+no_connect"))
    )
    (net (code "180") (name "unconnected-(U24-USIM_DATA-Pad10)") (class "Default")
      (node (ref "U24") (pin "10") (pinfunction "USIM_DATA_10") (pintype "passive+no_connect"))
    )
    (net (code "181") (name "unconnected-(U24-USIM_DET-Pad44)") (class "Default")
      (node (ref "U24") (pin "44") (pinfunction "USIM_DET_44") (pintype "passive+no_connect"))
    )
    (net (code "182") (name "unconnected-(U24-USIM_RST-Pad14)") (class "Default")
      (node (ref "U24") (pin "14") (pinfunction "USIM_RST_14") (pintype "passive+no_connect"))
    )
    (net (code "183") (name "unconnected-(U24-USIM_VDD-Pad8)") (class "Default")
      (node (ref "U24") (pin "8") (pinfunction "USIM_VDD_8") (pintype "passive+no_connect"))
    )
    (net (code "184") (name "unconnected-(U24-VDD_EXT-Pad11)") (class "Default")
      (node (ref "U24") (pin "11") (pinfunction "VDD_EXT_11") (pintype "passive+no_connect"))
    )
    (net (code "185") (name "unconnected-(U24-WAKEUP_OUT-Pad32)") (class "Default")
      (node (ref "U24") (pin "32") (pinfunction "WAKEUP_OUT_32") (pintype "passive+no_connect"))
    )
    (net (code "186") (name "unconnected-(U24-W_DISABLE#-Pad20)") (class "Default")
      (node (ref "U24") (pin "20") (pinfunction "W_DISABLE#_20") (pintype "passive+no_connect"))
    )
    (net (code "187") (name "unconnected-(U25-MIC_N-Pad3)") (class "Default")
      (node (ref "U25") (pin "3") (pinfunction "MIC_N_3") (pintype "passive+no_connect"))
    )
    (net (code "188") (name "unconnected-(U25-MIC_P-Pad1)") (class "Default")
      (node (ref "U25") (pin "1") (pinfunction "MIC_P_1") (pintype "passive+no_connect"))
    )
    (net (code "189") (name "unconnected-(U25-NC1-Pad6)") (class "Default")
      (node (ref "U25") (pin "6") (pinfunction "NC1_6") (pintype "passive+no_connect"))
    )
    (net (code "190") (name "unconnected-(U25-NC2-Pad48)") (class "Default")
      (node (ref "U25") (pin "48") (pinfunction "NC2_48") (pintype "passive+no_connect"))
    )
    (net (code "191") (name "unconnected-(U25-PESRT2#-Pad33)") (class "Default")
      (node (ref "U25") (pin "33") (pinfunction "PESRT2#_33") (pintype "passive"))
    )
    (net (code "192") (name "unconnected-(U25-RESERVED1-Pad13)") (class "Default")
      (node (ref "U25") (pin "13") (pinfunction "RESERVED1_13") (pintype "passive+no_connect"))
    )
    (net (code "193") (name "unconnected-(U25-RESERVED2-Pad16)") (class "Default")
      (node (ref "U25") (pin "16") (pinfunction "RESERVED2_16") (pintype "passive+no_connect"))
    )
    (net (code "194") (name "unconnected-(U25-RESERVED3-Pad17)") (class "Default")
      (node (ref "U25") (pin "17") (pinfunction "RESERVED3_17") (pintype "passive+no_connect"))
    )
    (net (code "195") (name "unconnected-(U25-RESERVED4-Pad45)") (class "Default")
      (node (ref "U25") (pin "45") (pinfunction "RESERVED4_45") (pintype "passive+no_connect"))
    )
    (net (code "196") (name "unconnected-(U25-RESERVED5-Pad47)") (class "Default")
      (node (ref "U25") (pin "47") (pinfunction "RESERVED5_47") (pintype "passive+no_connect"))
    )
    (net (code "197") (name "unconnected-(U25-RESERVED6-Pad49)") (class "Default")
      (node (ref "U25") (pin "49") (pinfunction "RESERVED6_49") (pintype "passive+no_connect"))
    )
    (net (code "198") (name "unconnected-(U25-RESERVED7-Pad51)") (class "Default")
      (node (ref "U25") (pin "51") (pinfunction "RESERVED7_51") (pintype "passive+no_connect"))
    )
    (net (code "199") (name "unconnected-(U25-SPK_N-Pad7)") (class "Default")
      (node (ref "U25") (pin "7") (pinfunction "SPK_N_7") (pintype "passive+no_connect"))
    )
    (net (code "200") (name "unconnected-(U25-SPK_P-Pad5)") (class "Default")
      (node (ref "U25") (pin "5") (pinfunction "SPK_P_5") (pintype "passive+no_connect"))
    )
    (net (code "201") (name "unconnected-(U25-UART_CTS-Pad28)") (class "Default")
      (node (ref "U25") (pin "28") (pinfunction "UART_CTS_28") (pintype "passive+no_connect"))
    )
    (net (code "202") (name "unconnected-(U25-UART_DCD-Pad30)") (class "Default")
      (node (ref "U25") (pin "30") (pinfunction "UART_DCD_30") (pintype "passive+no_connect"))
    )
    (net (code "203") (name "unconnected-(U25-UART_DTR-Pad46)") (class "Default")
      (node (ref "U25") (pin "46") (pinfunction "UART_DTR_46") (pintype "passive+no_connect"))
    )
    (net (code "204") (name "unconnected-(U25-UART_RTS-Pad25)") (class "Default")
      (node (ref "U25") (pin "25") (pinfunction "UART_RTS_25") (pintype "passive+no_connect"))
    )
    (net (code "205") (name "unconnected-(U25-UART_RXD-Pad23)") (class "Default")
      (node (ref "U25") (pin "23") (pinfunction "UART_RXD_23") (pintype "passive+no_connect"))
    )
    (net (code "206") (name "unconnected-(U25-UART_TXD-Pad31)") (class "Default")
      (node (ref "U25") (pin "31") (pinfunction "UART_TXD_31") (pintype "passive+no_connect"))
    )
    (net (code "207") (name "unconnected-(U25-WAKEUP_IN-Pad19)") (class "Default")
      (node (ref "U25") (pin "19") (pinfunction "WAKEUP_IN_19") (pintype "passive+no_connect"))
    )
    (net (code "208") (name "unconnected-(U25-WAKEUP_OUT-Pad32)") (class "Default")
      (node (ref "U25") (pin "32") (pinfunction "WAKEUP_OUT_32") (pintype "passive+no_connect"))
    )
    (net (code "209") (name "unconnected-(U25-W_DISABLE#-Pad20)") (class "Default")
      (node (ref "U25") (pin "20") (pinfunction "W_DISABLE#_20") (pintype "passive+no_connect"))
    )
    (net (code "210") (name "unconnected-(U26-GD02-Pad5)") (class "Default")
      (node (ref "U26") (pin "5") (pinfunction "GD02_5") (pintype "passive+no_connect"))
    )
    (net (code "211") (name "unconnected-(U26-NC-Pad10)") (class "Default")
      (node (ref "U26") (pin "10") (pinfunction "NC_10") (pintype "passive+no_connect"))
    )
    (net (code "212") (name "unconnected-(U28-ANTON-Pad13)") (class "Default")
      (node (ref "U28") (pin "13") (pinfunction "ANTON_13") (pintype "passive+no_connect"))
    )
    (net (code "213") (name "unconnected-(U28-RSVD{slash}NC-Pad7)") (class "Default")
      (node (ref "U28") (pin "7") (pinfunction "RSVD/NC_7") (pintype "passive+no_connect"))
    )
    (net (code "214") (name "unconnected-(U28-RSVD{slash}NC-Pad15)") (class "Default")
      (node (ref "U28") (pin "15") (pinfunction "RSVD/NC_15") (pintype "passive+no_connect"))
    )
    (net (code "215") (name "unconnected-(U28-RSVD{slash}NC-Pad16)") (class "Default")
      (node (ref "U28") (pin "16") (pinfunction "RSVD/NC_16") (pintype "passive+no_connect"))
    )
    (net (code "216") (name "unconnected-(U28-RSVD{slash}NC-Pad17)") (class "Default")
      (node (ref "U28") (pin "17") (pinfunction "RSVD/NC_17") (pintype "passive+no_connect"))
    )
    (net (code "217") (name "unconnected-(U32-NC-Pad8)") (class "Default")
      (node (ref "U32") (pin "8") (pinfunction "NC_8") (pintype "passive+no_connect"))
    )
    (net (code "218") (name "unconnected-(U32-NC-Pad9)") (class "Default")
      (node (ref "U32") (pin "9") (pinfunction "NC_9") (pintype "passive+no_connect"))
    )
    (net (code "219") (name "unconnected-(U32-P0.0-Pad23)") (class "Default")
      (node (ref "U32") (pin "23") (pinfunction "P0.0_23") (pintype "passive+no_connect"))
    )
    (net (code "220") (name "unconnected-(U32-P0.1-Pad22)") (class "Default")
      (node (ref "U32") (pin "22") (pinfunction "P0.1_22") (pintype "passive+no_connect"))
    )
    (net (code "221") (name "unconnected-(U32-P0.2-Pad21)") (class "Default")
      (node (ref "U32") (pin "21") (pinfunction "P0.2_21") (pintype "passive+no_connect"))
    )
    (net (code "222") (name "unconnected-(U32-P0.3-Pad20)") (class "Default")
      (node (ref "U32") (pin "20") (pinfunction "P0.3_20") (pintype "passive+no_connect"))
    )
    (net (code "223") (name "unconnected-(U32-P0.4-Pad19)") (class "Default")
      (node (ref "U32") (pin "19") (pinfunction "P0.4_19") (pintype "passive+no_connect"))
    )
    (net (code "224") (name "unconnected-(U32-P0.5-Pad18)") (class "Default")
      (node (ref "U32") (pin "18") (pinfunction "P0.5_18") (pintype "passive+no_connect"))
    )
    (net (code "225") (name "unconnected-(U32-P0.6-Pad17)") (class "Default")
      (node (ref "U32") (pin "17") (pinfunction "P0.6_17") (pintype "passive+no_connect"))
    )
    (net (code "226") (name "unconnected-(U32-P0.7-Pad16)") (class "Default")
      (node (ref "U32") (pin "16") (pinfunction "P0.7_16") (pintype "passive+no_connect"))
    )
    (net (code "227") (name "unconnected-(U32-P1.0-Pad15)") (class "Default")
      (node (ref "U32") (pin "15") (pinfunction "P1.0_15") (pintype "passive+no_connect"))
    )
    (net (code "228") (name "unconnected-(U32-P1.1-Pad14)") (class "Default")
      (node (ref "U32") (pin "14") (pinfunction "P1.1_14") (pintype "passive+no_connect"))
    )
    (net (code "229") (name "unconnected-(U32-P1.6-Pad7)") (class "Default")
      (node (ref "U32") (pin "7") (pinfunction "P1.6_7") (pintype "passive+no_connect"))
    )
    (net (code "230") (name "unconnected-(U32-P2.0-Pad5)") (class "Default")
      (node (ref "U32") (pin "5") (pinfunction "P2.0_5") (pintype "passive+no_connect"))
    )
    (net (code "231") (name "unconnected-(U32-P2.1-Pad4)") (class "Default")
      (node (ref "U32") (pin "4") (pinfunction "P2.1_4") (pintype "passive+no_connect"))
    )
    (net (code "232") (name "unconnected-(U32-P2.2-Pad3)") (class "Default")
      (node (ref "U32") (pin "3") (pinfunction "P2.2_3") (pintype "passive+no_connect"))
    )
  )
)
